# houston.net
KiCad netlist of a schematic drawn in EAGLE
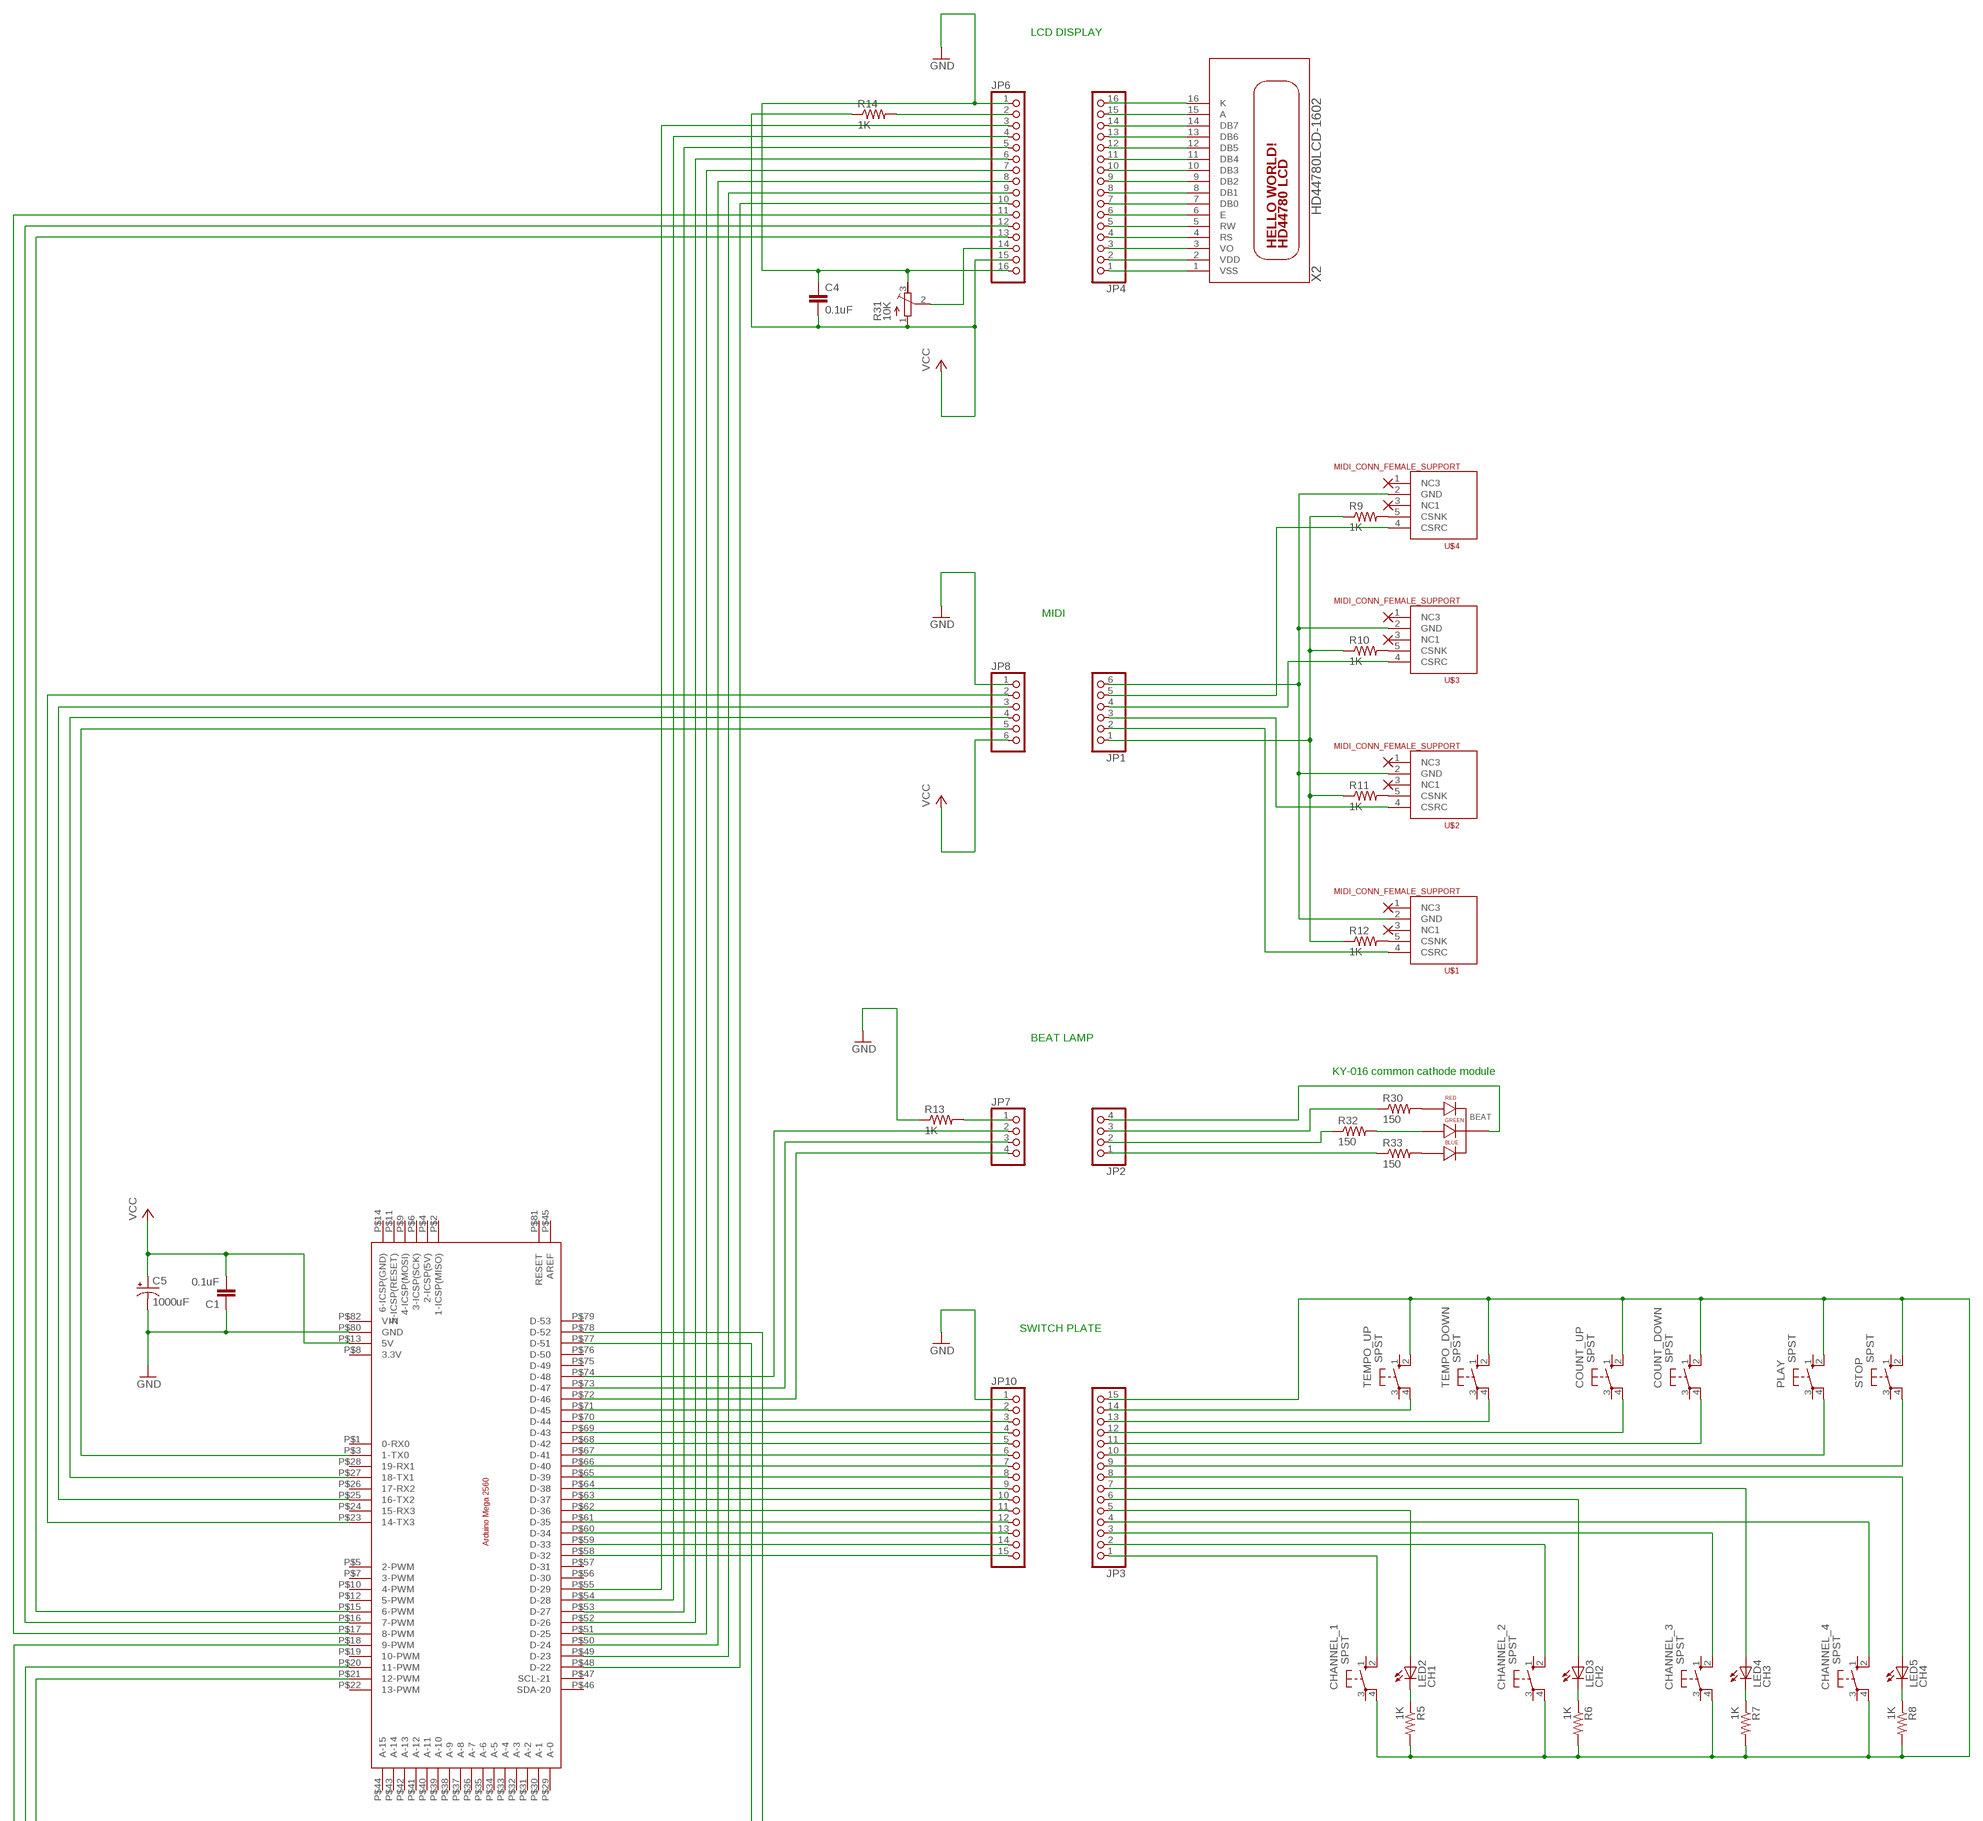
[diagram p0: schematic, sheet 1, part 1 of 3]
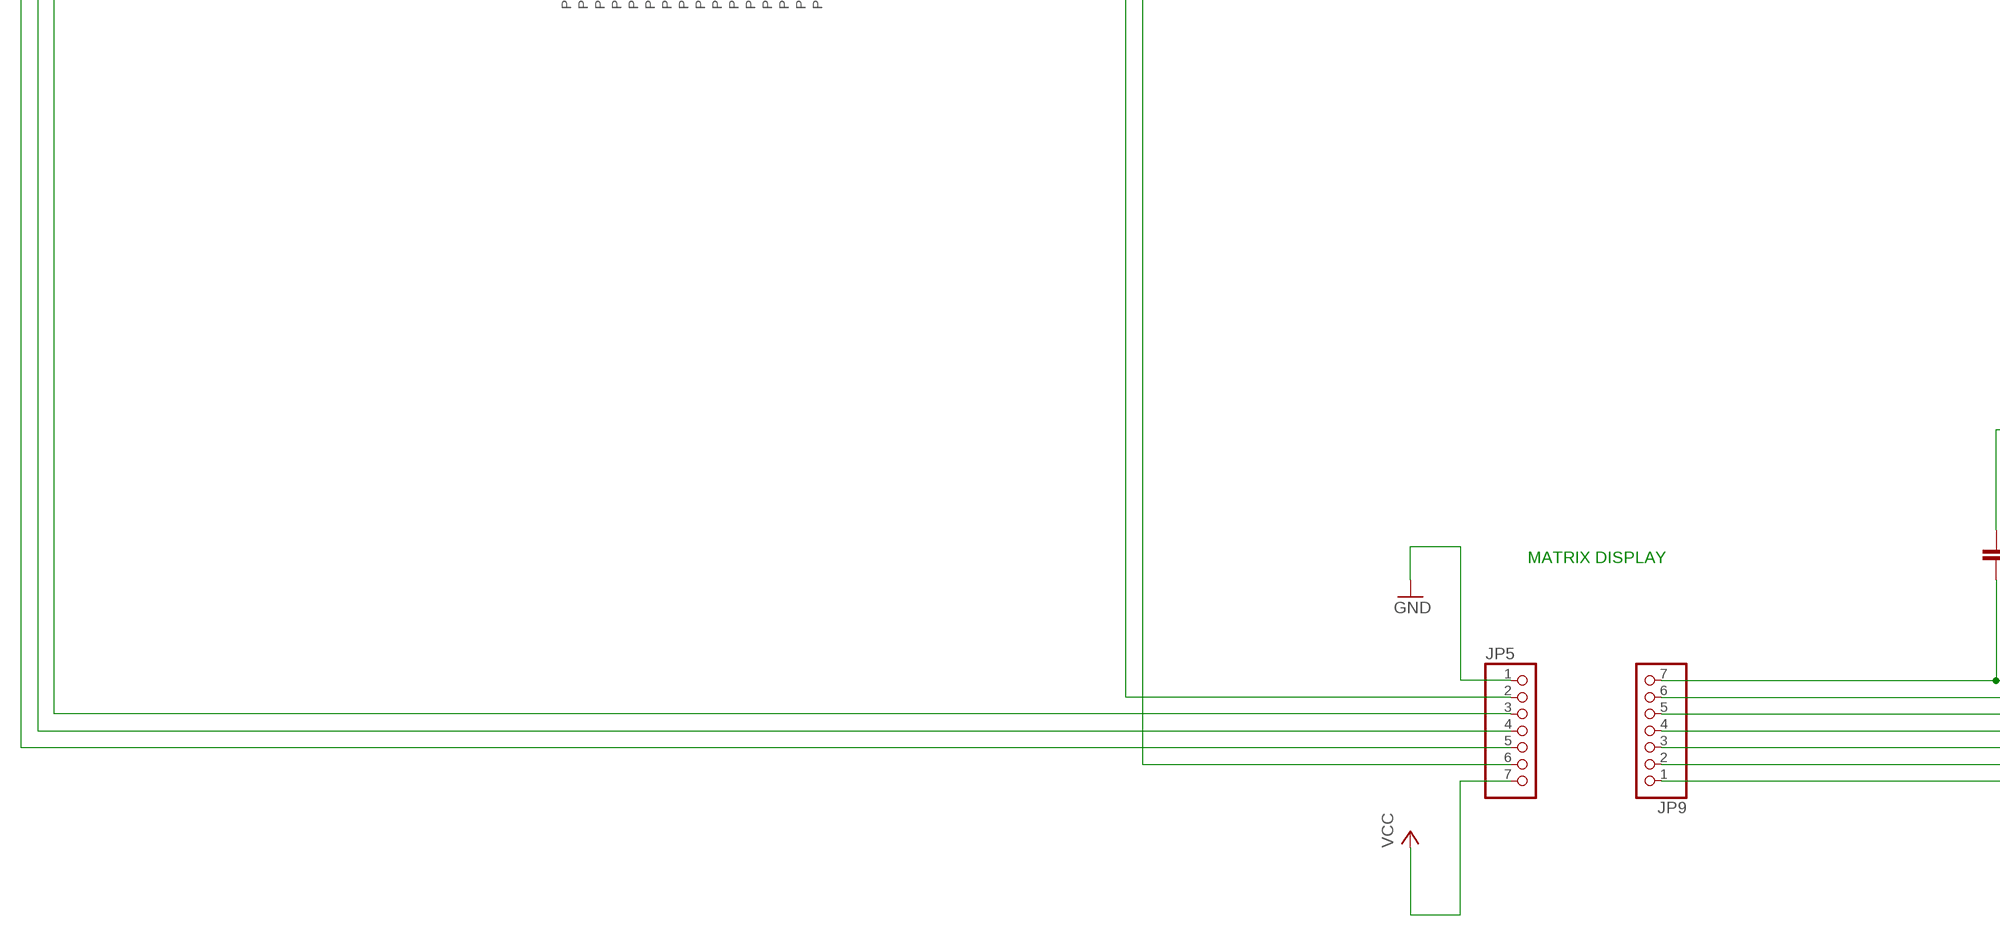
[diagram p1: schematic, sheet 1, part 2 of 3]
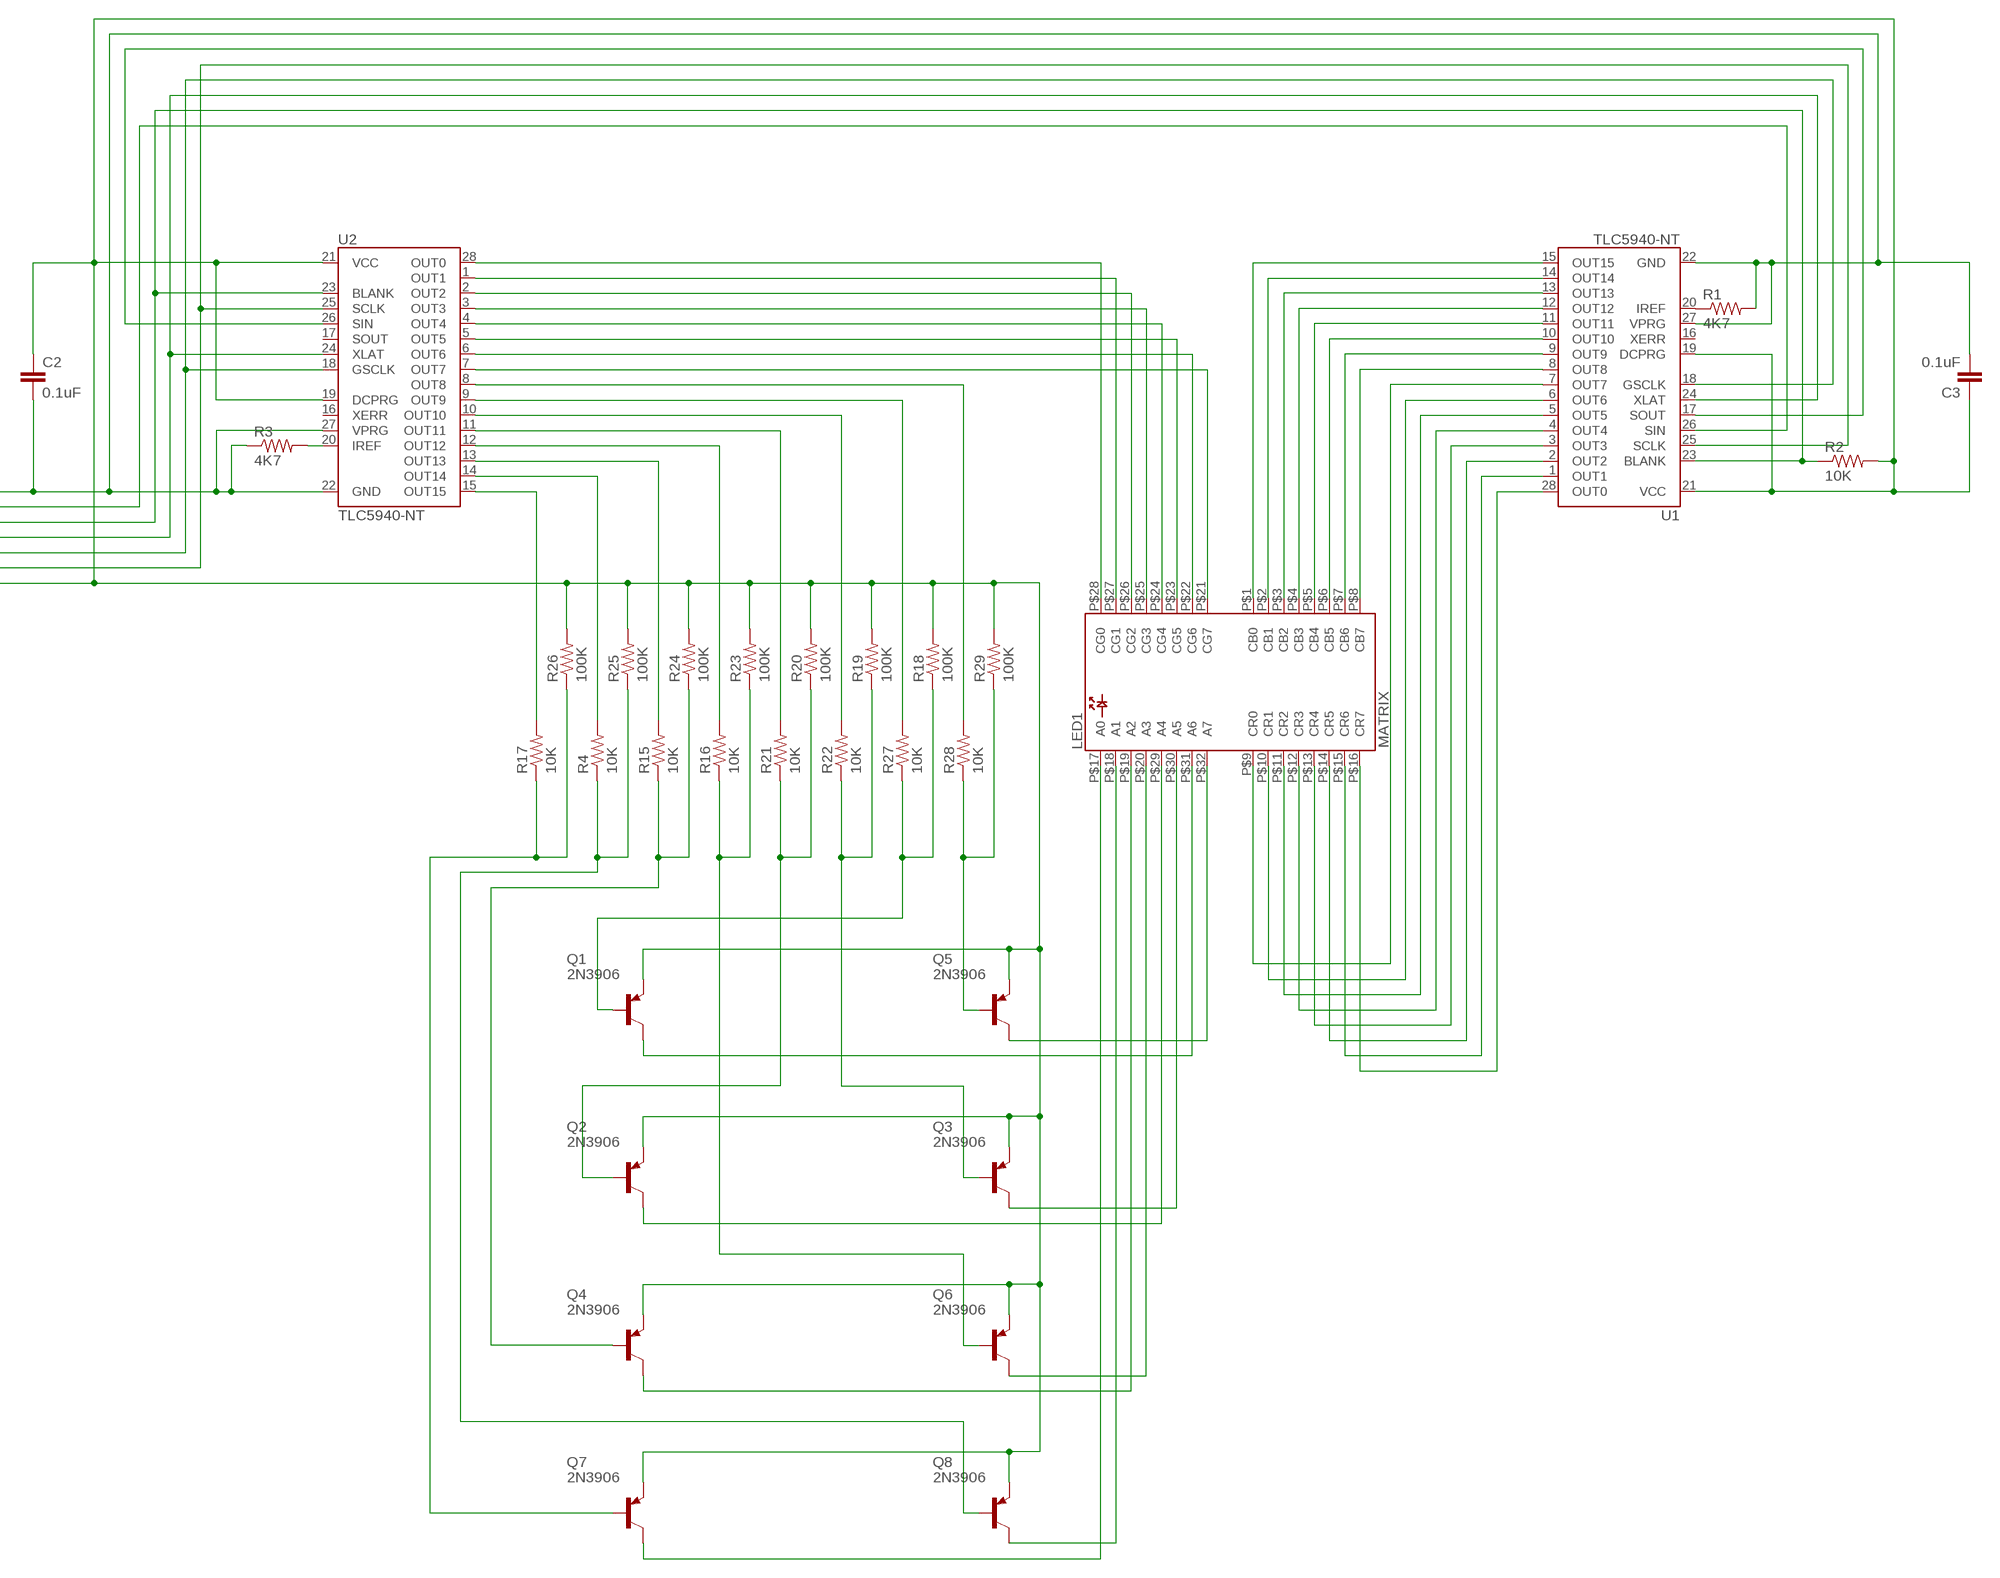
[diagram p2: schematic, sheet 1, part 3 of 3]

(export (version "E")
  (design (tool "Eeschema 10.0.6"))
  (components
    (comp (ref "BEAT")
      (value "LED-RGB-CC-THRUCLEAR")
      (footprint "eagle-import:LED-RGB-THRU")
      (libsource (lib "eagle-import") (part "LED-RGB-CC-THRUCLEAR"))
    )
    (comp (ref "C1")
      (value "0.1uF")
      (footprint "eagle-import:CAP-PTH-SMALLEZ")
      (libsource (lib "eagle-import") (part "CAPEZ"))
    )
    (comp (ref "C2")
      (value "0.1uF")
      (footprint "eagle-import:CAP-PTH-SMALLEZ")
      (libsource (lib "eagle-import") (part "CAPEZ"))
    )
    (comp (ref "C3")
      (value "0.1uF")
      (footprint "eagle-import:CAP-PTH-SMALLEZ")
      (libsource (lib "eagle-import") (part "CAPEZ"))
    )
    (comp (ref "C4")
      (value "0.1uF")
      (footprint "eagle-import:CAP-PTH-SMALLEZ")
      (libsource (lib "eagle-import") (part "CAPEZ"))
    )
    (comp (ref "C5")
      (value "1000uF")
      (footprint "eagle-import:CPOL-RADIAL-1000UF-25V")
      (libsource (lib "eagle-import") (part "CAP_POLPTH4"))
    )
    (comp (ref "CHANNEL_1")
      (value "SPST")
      (footprint "eagle-import:B3F-40XX-ROUND")
      (libsource (lib "eagle-import") (part "40-XX-ROUND"))
    )
    (comp (ref "CHANNEL_2")
      (value "SPST")
      (footprint "eagle-import:B3F-40XX-ROUND")
      (libsource (lib "eagle-import") (part "40-XX-ROUND"))
    )
    (comp (ref "CHANNEL_3")
      (value "SPST")
      (footprint "eagle-import:B3F-40XX-ROUND")
      (libsource (lib "eagle-import") (part "40-XX-ROUND"))
    )
    (comp (ref "CHANNEL_4")
      (value "SPST")
      (footprint "eagle-import:B3F-40XX-ROUND")
      (libsource (lib "eagle-import") (part "40-XX-ROUND"))
    )
    (comp (ref "COUNT_DOWN")
      (value "SPST")
      (footprint "eagle-import:B3F-40XX-ROUND")
      (libsource (lib "eagle-import") (part "40-XX-ROUND"))
    )
    (comp (ref "COUNT_UP")
      (value "SPST")
      (footprint "eagle-import:B3F-40XX-ROUND")
      (libsource (lib "eagle-import") (part "40-XX-ROUND"))
    )
    (comp (ref "JP1")
      (value "PINHD-1X6/90")
      (footprint "eagle-import:1X06_90")
      (libsource (lib "eagle-import") (part "PINHD-1X6/90"))
    )
    (comp (ref "JP2")
      (value "PINHD-1X4/90")
      (footprint "eagle-import:1X04_90")
      (libsource (lib "eagle-import") (part "PINHD-1X4/90"))
    )
    (comp (ref "JP3")
      (value "PINHD-1X15/90")
      (footprint "eagle-import:1X15_90")
      (libsource (lib "eagle-import") (part "PINHD-1X15/90"))
    )
    (comp (ref "JP4")
      (value "PINHD-1X16")
      (footprint "eagle-import:1X16")
      (libsource (lib "eagle-import") (part "PINHD-1X16"))
    )
    (comp (ref "JP5")
      (value "PINHD-1X7")
      (footprint "eagle-import:1X07")
      (libsource (lib "eagle-import") (part "PINHD-1X7"))
    )
    (comp (ref "JP6")
      (value "PINHD-1X16")
      (footprint "eagle-import:1X16")
      (libsource (lib "eagle-import") (part "PINHD-1X16"))
    )
    (comp (ref "JP7")
      (value "PINHD-1X4")
      (footprint "eagle-import:1X04")
      (libsource (lib "eagle-import") (part "PINHD-1X4"))
    )
    (comp (ref "JP8")
      (value "PINHD-1X6")
      (footprint "eagle-import:1X06")
      (libsource (lib "eagle-import") (part "PINHD-1X6"))
    )
    (comp (ref "JP9")
      (value "PINHD-1X7/90")
      (footprint "eagle-import:1X07_90")
      (libsource (lib "eagle-import") (part "PINHD-1X7/90"))
    )
    (comp (ref "JP10")
      (value "PINHD-1X15-CB")
      (footprint "eagle-import:1X15-CB")
      (libsource (lib "eagle-import") (part "PINHD-1X15-CB"))
    )
    (comp (ref "LED1")
      (value "MATRIX")
      (footprint "eagle-import:ORM-2088-RGB-5")
      (libsource (lib "eagle-import") (part "ORM-2088-RGB-5"))
    )
    (comp (ref "LED2")
      (value "CH1")
      (footprint "eagle-import:LED3MM")
      (libsource (lib "eagle-import") (part "LED3MM"))
    )
    (comp (ref "LED3")
      (value "CH2")
      (footprint "eagle-import:LED3MM")
      (libsource (lib "eagle-import") (part "LED3MM"))
    )
    (comp (ref "LED4")
      (value "CH3")
      (footprint "eagle-import:LED3MM")
      (libsource (lib "eagle-import") (part "LED3MM"))
    )
    (comp (ref "LED5")
      (value "CH4")
      (footprint "eagle-import:LED3MM")
      (libsource (lib "eagle-import") (part "LED3MM"))
    )
    (comp (ref "PLAY")
      (value "SPST")
      (footprint "eagle-import:B3F-40XX-ROUND")
      (libsource (lib "eagle-import") (part "40-XX-ROUND"))
    )
    (comp (ref "Q1")
      (value "2N3906")
      (footprint "eagle-import:TO92")
      (libsource (lib "eagle-import") (part "2N3906"))
    )
    (comp (ref "Q2")
      (value "2N3906")
      (footprint "eagle-import:TO92")
      (libsource (lib "eagle-import") (part "2N3906"))
    )
    (comp (ref "Q3")
      (value "2N3906")
      (footprint "eagle-import:TO92")
      (libsource (lib "eagle-import") (part "2N3906"))
    )
    (comp (ref "Q4")
      (value "2N3906")
      (footprint "eagle-import:TO92")
      (libsource (lib "eagle-import") (part "2N3906"))
    )
    (comp (ref "Q5")
      (value "2N3906")
      (footprint "eagle-import:TO92")
      (libsource (lib "eagle-import") (part "2N3906"))
    )
    (comp (ref "Q6")
      (value "2N3906")
      (footprint "eagle-import:TO92")
      (libsource (lib "eagle-import") (part "2N3906"))
    )
    (comp (ref "Q7")
      (value "2N3906")
      (footprint "eagle-import:TO92")
      (libsource (lib "eagle-import") (part "2N3906"))
    )
    (comp (ref "Q8")
      (value "2N3906")
      (footprint "eagle-import:TO92")
      (libsource (lib "eagle-import") (part "2N3906"))
    )
    (comp (ref "R1")
      (value "4K7")
      (footprint "eagle-import:0411V")
      (libsource (lib "eagle-import") (part "R-US_0411/3V"))
    )
    (comp (ref "R2")
      (value "10K")
      (footprint "eagle-import:0411V")
      (libsource (lib "eagle-import") (part "R-US_0411/3V"))
    )
    (comp (ref "R3")
      (value "4K7")
      (footprint "eagle-import:0411V")
      (libsource (lib "eagle-import") (part "R-US_0411/3V"))
    )
    (comp (ref "R4")
      (value "10K")
      (footprint "eagle-import:0207_10")
      (libsource (lib "eagle-import") (part "resistor_R-US_0207/10"))
    )
    (comp (ref "R5")
      (value "1K")
      (footprint "eagle-import:0204_7")
      (libsource (lib "eagle-import") (part "resistor_R-US_0204/7"))
    )
    (comp (ref "R6")
      (value "1K")
      (footprint "eagle-import:0204_7")
      (libsource (lib "eagle-import") (part "resistor_R-US_0204/7"))
    )
    (comp (ref "R7")
      (value "1K")
      (footprint "eagle-import:0204_7")
      (libsource (lib "eagle-import") (part "resistor_R-US_0204/7"))
    )
    (comp (ref "R8")
      (value "1K")
      (footprint "eagle-import:0204_7")
      (libsource (lib "eagle-import") (part "resistor_R-US_0204/7"))
    )
    (comp (ref "R9")
      (value "1K")
      (footprint "eagle-import:0207_2V")
      (libsource (lib "eagle-import") (part "resistor_R-US_0207/2V"))
    )
    (comp (ref "R10")
      (value "1K")
      (footprint "eagle-import:0207_2V")
      (libsource (lib "eagle-import") (part "resistor_R-US_0207/2V"))
    )
    (comp (ref "R11")
      (value "1K")
      (footprint "eagle-import:0207_2V")
      (libsource (lib "eagle-import") (part "resistor_R-US_0207/2V"))
    )
    (comp (ref "R12")
      (value "1K")
      (footprint "eagle-import:0207_2V")
      (libsource (lib "eagle-import") (part "resistor_R-US_0207/2V"))
    )
    (comp (ref "R13")
      (value "1K")
      (footprint "eagle-import:0207_2V")
      (libsource (lib "eagle-import") (part "resistor_R-US_0207/2V"))
    )
    (comp (ref "R14")
      (value "1K")
      (footprint "eagle-import:0204_7")
      (libsource (lib "eagle-import") (part "rcl_R-US_0204/7"))
    )
    (comp (ref "R15")
      (value "10K")
      (footprint "eagle-import:0207_10")
      (libsource (lib "eagle-import") (part "resistor_R-US_0207/10"))
    )
    (comp (ref "R16")
      (value "10K")
      (footprint "eagle-import:0207_10")
      (libsource (lib "eagle-import") (part "resistor_R-US_0207/10"))
    )
    (comp (ref "R17")
      (value "10K")
      (footprint "eagle-import:0207_10")
      (libsource (lib "eagle-import") (part "resistor_R-US_0207/10"))
    )
    (comp (ref "R18")
      (value "100K")
      (footprint "eagle-import:0207_10")
      (libsource (lib "eagle-import") (part "resistor_R-US_0207/10"))
    )
    (comp (ref "R19")
      (value "100K")
      (footprint "eagle-import:0207_10")
      (libsource (lib "eagle-import") (part "resistor_R-US_0207/10"))
    )
    (comp (ref "R20")
      (value "100K")
      (footprint "eagle-import:0207_10")
      (libsource (lib "eagle-import") (part "resistor_R-US_0207/10"))
    )
    (comp (ref "R21")
      (value "10K")
      (footprint "eagle-import:0207_10")
      (libsource (lib "eagle-import") (part "resistor_R-US_0207/10"))
    )
    (comp (ref "R22")
      (value "10K")
      (footprint "eagle-import:0207_10")
      (libsource (lib "eagle-import") (part "resistor_R-US_0207/10"))
    )
    (comp (ref "R23")
      (value "100K")
      (footprint "eagle-import:0207_10")
      (libsource (lib "eagle-import") (part "resistor_R-US_0207/10"))
    )
    (comp (ref "R24")
      (value "100K")
      (footprint "eagle-import:0207_10")
      (libsource (lib "eagle-import") (part "resistor_R-US_0207/10"))
    )
    (comp (ref "R25")
      (value "100K")
      (footprint "eagle-import:0207_10")
      (libsource (lib "eagle-import") (part "resistor_R-US_0207/10"))
    )
    (comp (ref "R26")
      (value "100K")
      (footprint "eagle-import:0207_10")
      (libsource (lib "eagle-import") (part "resistor_R-US_0207/10"))
    )
    (comp (ref "R27")
      (value "10K")
      (footprint "eagle-import:0207_10")
      (libsource (lib "eagle-import") (part "resistor_R-US_0207/10"))
    )
    (comp (ref "R28")
      (value "10K")
      (footprint "eagle-import:0207_10")
      (libsource (lib "eagle-import") (part "resistor_R-US_0207/10"))
    )
    (comp (ref "R29")
      (value "100K")
      (footprint "eagle-import:0207_10")
      (libsource (lib "eagle-import") (part "resistor_R-US_0207/10"))
    )
    (comp (ref "R30")
      (value "150")
      (footprint "eagle-import:0204_7")
      (libsource (lib "eagle-import") (part "R-US_0204/7"))
    )
    (comp (ref "R31")
      (value "10K")
      (footprint "eagle-import:RTRIM3296W")
      (libsource (lib "eagle-import") (part "R-TRIMM3296W"))
    )
    (comp (ref "R32")
      (value "150")
      (footprint "eagle-import:0204_7")
      (libsource (lib "eagle-import") (part "R-US_0204/7"))
    )
    (comp (ref "R33")
      (value "150")
      (footprint "eagle-import:0204_7")
      (libsource (lib "eagle-import") (part "R-US_0204/7"))
    )
    (comp (ref "STOP")
      (value "SPST")
      (footprint "eagle-import:B3F-40XX-ROUND")
      (libsource (lib "eagle-import") (part "40-XX-ROUND"))
    )
    (comp (ref "TEMPO_DOWN")
      (value "SPST")
      (footprint "eagle-import:B3F-40XX-ROUND")
      (libsource (lib "eagle-import") (part "40-XX-ROUND"))
    )
    (comp (ref "TEMPO_UP")
      (value "SPST")
      (footprint "eagle-import:B3F-40XX-ROUND")
      (libsource (lib "eagle-import") (part "40-XX-ROUND"))
    )
    (comp (ref "U$1")
      (value "MIDI_CONN_FEMALE_SUPPORT")
      (footprint "eagle-import:DIN_5_FEMALE_SUPPORT")
      (libsource (lib "eagle-import") (part "MIDI_CONN_FEMALE_SUPPORT"))
    )
    (comp (ref "U$2")
      (value "MIDI_CONN_FEMALE_SUPPORT")
      (footprint "eagle-import:DIN_5_FEMALE_SUPPORT")
      (libsource (lib "eagle-import") (part "MIDI_CONN_FEMALE_SUPPORT"))
    )
    (comp (ref "U$3")
      (value "MIDI_CONN_FEMALE_SUPPORT")
      (footprint "eagle-import:DIN_5_FEMALE_SUPPORT")
      (libsource (lib "eagle-import") (part "MIDI_CONN_FEMALE_SUPPORT"))
    )
    (comp (ref "U$4")
      (value "MIDI_CONN_FEMALE_SUPPORT")
      (footprint "eagle-import:DIN_5_FEMALE_SUPPORT")
      (libsource (lib "eagle-import") (part "MIDI_CONN_FEMALE_SUPPORT"))
    )
    (comp (ref "U$6")
      (value "2560")
      (footprint "eagle-import:MEDUINO2560")
      (libsource (lib "eagle-import") (part "2560"))
    )
    (comp (ref "U1")
      (value "TLC5940-NT")
      (footprint "eagle-import:DIL28-3")
      (libsource (lib "eagle-import") (part "TLC5940-NT"))
    )
    (comp (ref "U2")
      (value "TLC5940-NT")
      (footprint "eagle-import:DIL28-3")
      (libsource (lib "eagle-import") (part "TLC5940-NT"))
    )
    (comp (ref "X2")
      (value "HD44780LCD-1602")
      (footprint "eagle-import:LCD1602")
      (libsource (lib "eagle-import") (part "HD44780LCD-1602"))
    )
  )
  (nets
    (net (code "1") (name "GND") (class "Default")
      (node (ref "C1") (pin "1") (pinfunction "1_1") (pintype "passive"))
      (node (ref "C4") (pin "1") (pinfunction "1_1") (pintype "passive"))
      (node (ref "C5") (pin "2") (pinfunction "-_2") (pintype "passive"))
      (node (ref "JP10") (pin "1") (pinfunction "1_1") (pintype "passive"))
      (node (ref "JP5") (pin "1") (pinfunction "1_1") (pintype "passive"))
      (node (ref "JP6") (pin "1") (pinfunction "1_1") (pintype "passive"))
      (node (ref "JP6") (pin "16") (pinfunction "16_16") (pintype "passive"))
      (node (ref "JP8") (pin "1") (pinfunction "1_1") (pintype "passive"))
      (node (ref "R13") (pin "1") (pinfunction "1_1") (pintype "passive"))
      (node (ref "R31") (pin "3") (pinfunction "E_3") (pintype "passive"))
      (node (ref "U$6") (pin "P$80") (pinfunction "GND_P$80") (pintype "bidirectional"))
    )
    (net (code "2") (name "Net-(BEAT-BLUE_CATHODE)") (class "Default")
      (node (ref "BEAT") (pin "4") (pinfunction "BLUE_CATHODE_4") (pintype "bidirectional"))
      (node (ref "R33") (pin "2") (pinfunction "2_2") (pintype "passive"))
    )
    (net (code "3") (name "Net-(BEAT-CATHODE)") (class "Default")
      (node (ref "BEAT") (pin "2") (pinfunction "CATHODE_2") (pintype "bidirectional"))
      (node (ref "JP2") (pin "4") (pinfunction "4_4") (pintype "passive"))
    )
    (net (code "4") (name "Net-(BEAT-GREEN_CATHODE)") (class "Default")
      (node (ref "BEAT") (pin "3") (pinfunction "GREEN_CATHODE_3") (pintype "bidirectional"))
      (node (ref "R32") (pin "2") (pinfunction "2_2") (pintype "passive"))
    )
    (net (code "5") (name "Net-(BEAT-RED_CATHODE)") (class "Default")
      (node (ref "BEAT") (pin "1") (pinfunction "RED_CATHODE_1") (pintype "bidirectional"))
      (node (ref "R30") (pin "2") (pinfunction "2_2") (pintype "passive"))
    )
    (net (code "6") (name "Net-(CHANNEL_1-P1)") (class "Default")
      (node (ref "CHANNEL_1") (pin "4") (pinfunction "P1_4") (pintype "passive"))
      (node (ref "CHANNEL_2") (pin "4") (pinfunction "P1_4") (pintype "passive"))
      (node (ref "CHANNEL_3") (pin "4") (pinfunction "P1_4") (pintype "passive"))
      (node (ref "CHANNEL_4") (pin "4") (pinfunction "P1_4") (pintype "passive"))
      (node (ref "COUNT_DOWN") (pin "2") (pinfunction "S1_2") (pintype "passive"))
      (node (ref "COUNT_UP") (pin "2") (pinfunction "S1_2") (pintype "passive"))
      (node (ref "JP3") (pin "15") (pinfunction "15_15") (pintype "passive"))
      (node (ref "PLAY") (pin "2") (pinfunction "S1_2") (pintype "passive"))
      (node (ref "R5") (pin "2") (pinfunction "2_2") (pintype "passive"))
      (node (ref "R6") (pin "2") (pinfunction "2_2") (pintype "passive"))
      (node (ref "R7") (pin "2") (pinfunction "2_2") (pintype "passive"))
      (node (ref "R8") (pin "2") (pinfunction "2_2") (pintype "passive"))
      (node (ref "STOP") (pin "2") (pinfunction "S1_2") (pintype "passive"))
      (node (ref "TEMPO_DOWN") (pin "2") (pinfunction "S1_2") (pintype "passive"))
      (node (ref "TEMPO_UP") (pin "2") (pinfunction "S1_2") (pintype "passive"))
    )
    (net (code "7") (name "Net-(CHANNEL_1-S1)") (class "Default")
      (node (ref "CHANNEL_1") (pin "2") (pinfunction "S1_2") (pintype "passive"))
      (node (ref "JP3") (pin "1") (pinfunction "1_1") (pintype "passive"))
    )
    (net (code "8") (name "Net-(CHANNEL_2-S1)") (class "Default")
      (node (ref "CHANNEL_2") (pin "2") (pinfunction "S1_2") (pintype "passive"))
      (node (ref "JP3") (pin "2") (pinfunction "2_2") (pintype "passive"))
    )
    (net (code "9") (name "Net-(CHANNEL_3-S1)") (class "Default")
      (node (ref "CHANNEL_3") (pin "2") (pinfunction "S1_2") (pintype "passive"))
      (node (ref "JP3") (pin "3") (pinfunction "3_3") (pintype "passive"))
    )
    (net (code "10") (name "Net-(CHANNEL_4-S1)") (class "Default")
      (node (ref "CHANNEL_4") (pin "2") (pinfunction "S1_2") (pintype "passive"))
      (node (ref "JP3") (pin "4") (pinfunction "4_4") (pintype "passive"))
    )
    (net (code "11") (name "Net-(COUNT_DOWN-P1)") (class "Default")
      (node (ref "COUNT_DOWN") (pin "4") (pinfunction "P1_4") (pintype "passive"))
      (node (ref "JP3") (pin "11") (pinfunction "11_11") (pintype "passive"))
    )
    (net (code "12") (name "Net-(COUNT_UP-P1)") (class "Default")
      (node (ref "COUNT_UP") (pin "4") (pinfunction "P1_4") (pintype "passive"))
      (node (ref "JP3") (pin "12") (pinfunction "12_12") (pintype "passive"))
    )
    (net (code "13") (name "Net-(JP1-Pad1)") (class "Default")
      (node (ref "JP1") (pin "1") (pinfunction "1_1") (pintype "passive"))
      (node (ref "R10") (pin "1") (pinfunction "1_1") (pintype "passive"))
      (node (ref "R11") (pin "1") (pinfunction "1_1") (pintype "passive"))
      (node (ref "R12") (pin "1") (pinfunction "1_1") (pintype "passive"))
      (node (ref "R9") (pin "1") (pinfunction "1_1") (pintype "passive"))
    )
    (net (code "14") (name "Net-(JP2-Pad1)") (class "Default")
      (node (ref "JP2") (pin "1") (pinfunction "1_1") (pintype "passive"))
      (node (ref "R33") (pin "1") (pinfunction "1_1") (pintype "passive"))
    )
    (net (code "15") (name "Net-(JP2-Pad2)") (class "Default")
      (node (ref "JP2") (pin "2") (pinfunction "2_2") (pintype "passive"))
      (node (ref "R32") (pin "1") (pinfunction "1_1") (pintype "passive"))
    )
    (net (code "16") (name "Net-(JP2-Pad3)") (class "Default")
      (node (ref "JP2") (pin "3") (pinfunction "3_3") (pintype "passive"))
      (node (ref "R30") (pin "1") (pinfunction "1_1") (pintype "passive"))
    )
    (net (code "17") (name "Net-(JP3-Pad5)") (class "Default")
      (node (ref "JP3") (pin "5") (pinfunction "5_5") (pintype "passive"))
      (node (ref "LED2") (pin "A") (pinfunction "A_A") (pintype "passive"))
    )
    (net (code "18") (name "Net-(JP3-Pad6)") (class "Default")
      (node (ref "JP3") (pin "6") (pinfunction "6_6") (pintype "passive"))
      (node (ref "LED3") (pin "A") (pinfunction "A_A") (pintype "passive"))
    )
    (net (code "19") (name "Net-(JP3-Pad7)") (class "Default")
      (node (ref "JP3") (pin "7") (pinfunction "7_7") (pintype "passive"))
      (node (ref "LED4") (pin "A") (pinfunction "A_A") (pintype "passive"))
    )
    (net (code "20") (name "Net-(JP3-Pad8)") (class "Default")
      (node (ref "JP3") (pin "8") (pinfunction "8_8") (pintype "passive"))
      (node (ref "LED5") (pin "A") (pinfunction "A_A") (pintype "passive"))
    )
    (net (code "21") (name "Net-(JP6-Pad2)") (class "Default")
      (node (ref "JP6") (pin "2") (pinfunction "2_2") (pintype "passive"))
      (node (ref "R14") (pin "2") (pinfunction "2_2") (pintype "passive"))
    )
    (net (code "22") (name "Net-(JP7-Pad1)") (class "Default")
      (node (ref "JP7") (pin "1") (pinfunction "1_1") (pintype "passive"))
      (node (ref "R13") (pin "2") (pinfunction "2_2") (pintype "passive"))
    )
    (net (code "23") (name "Net-(LED1-A0)") (class "Default")
      (node (ref "LED1") (pin "P$17") (pinfunction "A0_P$17") (pintype "bidirectional"))
      (node (ref "Q7") (pin "1") (pinfunction "C_1") (pintype "passive"))
    )
    (net (code "24") (name "Net-(LED1-A1)") (class "Default")
      (node (ref "LED1") (pin "P$18") (pinfunction "A1_P$18") (pintype "bidirectional"))
      (node (ref "Q8") (pin "1") (pinfunction "C_1") (pintype "passive"))
    )
    (net (code "25") (name "Net-(LED1-A2)") (class "Default")
      (node (ref "LED1") (pin "P$19") (pinfunction "A2_P$19") (pintype "bidirectional"))
      (node (ref "Q4") (pin "1") (pinfunction "C_1") (pintype "passive"))
    )
    (net (code "26") (name "Net-(LED1-A3)") (class "Default")
      (node (ref "LED1") (pin "P$20") (pinfunction "A3_P$20") (pintype "bidirectional"))
      (node (ref "Q6") (pin "1") (pinfunction "C_1") (pintype "passive"))
    )
    (net (code "27") (name "Net-(LED1-A4)") (class "Default")
      (node (ref "LED1") (pin "P$29") (pinfunction "A4_P$29") (pintype "bidirectional"))
      (node (ref "Q2") (pin "1") (pinfunction "C_1") (pintype "passive"))
    )
    (net (code "28") (name "Net-(LED1-A5)") (class "Default")
      (node (ref "LED1") (pin "P$30") (pinfunction "A5_P$30") (pintype "bidirectional"))
      (node (ref "Q3") (pin "1") (pinfunction "C_1") (pintype "passive"))
    )
    (net (code "29") (name "Net-(LED1-A6)") (class "Default")
      (node (ref "LED1") (pin "P$31") (pinfunction "A6_P$31") (pintype "bidirectional"))
      (node (ref "Q1") (pin "1") (pinfunction "C_1") (pintype "passive"))
    )
    (net (code "30") (name "Net-(LED1-A7)") (class "Default")
      (node (ref "LED1") (pin "P$32") (pinfunction "A7_P$32") (pintype "bidirectional"))
      (node (ref "Q5") (pin "1") (pinfunction "C_1") (pintype "passive"))
    )
    (net (code "31") (name "Net-(LED1-CB0)") (class "Default")
      (node (ref "LED1") (pin "P$1") (pinfunction "CB0_P$1") (pintype "bidirectional"))
      (node (ref "U1") (pin "15") (pinfunction "OUT15_15") (pintype "bidirectional"))
    )
    (net (code "32") (name "Net-(LED1-CB1)") (class "Default")
      (node (ref "LED1") (pin "P$2") (pinfunction "CB1_P$2") (pintype "bidirectional"))
      (node (ref "U1") (pin "14") (pinfunction "OUT14_14") (pintype "bidirectional"))
    )
    (net (code "33") (name "Net-(LED1-CB2)") (class "Default")
      (node (ref "LED1") (pin "P$3") (pinfunction "CB2_P$3") (pintype "bidirectional"))
      (node (ref "U1") (pin "13") (pinfunction "OUT13_13") (pintype "bidirectional"))
    )
    (net (code "34") (name "Net-(LED1-CB3)") (class "Default")
      (node (ref "LED1") (pin "P$4") (pinfunction "CB3_P$4") (pintype "bidirectional"))
      (node (ref "U1") (pin "12") (pinfunction "OUT12_12") (pintype "bidirectional"))
    )
    (net (code "35") (name "Net-(LED1-CB4)") (class "Default")
      (node (ref "LED1") (pin "P$5") (pinfunction "CB4_P$5") (pintype "bidirectional"))
      (node (ref "U1") (pin "11") (pinfunction "OUT11_11") (pintype "bidirectional"))
    )
    (net (code "36") (name "Net-(LED1-CB5)") (class "Default")
      (node (ref "LED1") (pin "P$6") (pinfunction "CB5_P$6") (pintype "bidirectional"))
      (node (ref "U1") (pin "10") (pinfunction "OUT10_10") (pintype "bidirectional"))
    )
    (net (code "37") (name "Net-(LED1-CB6)") (class "Default")
      (node (ref "LED1") (pin "P$7") (pinfunction "CB6_P$7") (pintype "bidirectional"))
      (node (ref "U1") (pin "9") (pinfunction "OUT9_9") (pintype "bidirectional"))
    )
    (net (code "38") (name "Net-(LED1-CB7)") (class "Default")
      (node (ref "LED1") (pin "P$8") (pinfunction "CB7_P$8") (pintype "bidirectional"))
      (node (ref "U1") (pin "8") (pinfunction "OUT8_8") (pintype "bidirectional"))
    )
    (net (code "39") (name "Net-(LED1-CG0)") (class "Default")
      (node (ref "LED1") (pin "P$28") (pinfunction "CG0_P$28") (pintype "bidirectional"))
      (node (ref "U2") (pin "28") (pinfunction "OUT0_28") (pintype "bidirectional"))
    )
    (net (code "40") (name "Net-(LED1-CG1)") (class "Default")
      (node (ref "LED1") (pin "P$27") (pinfunction "CG1_P$27") (pintype "bidirectional"))
      (node (ref "U2") (pin "1") (pinfunction "OUT1_1") (pintype "bidirectional"))
    )
    (net (code "41") (name "Net-(LED1-CG2)") (class "Default")
      (node (ref "LED1") (pin "P$26") (pinfunction "CG2_P$26") (pintype "bidirectional"))
      (node (ref "U2") (pin "2") (pinfunction "OUT2_2") (pintype "bidirectional"))
    )
    (net (code "42") (name "Net-(LED1-CG3)") (class "Default")
      (node (ref "LED1") (pin "P$25") (pinfunction "CG3_P$25") (pintype "bidirectional"))
      (node (ref "U2") (pin "3") (pinfunction "OUT3_3") (pintype "bidirectional"))
    )
    (net (code "43") (name "Net-(LED1-CG4)") (class "Default")
      (node (ref "LED1") (pin "P$24") (pinfunction "CG4_P$24") (pintype "bidirectional"))
      (node (ref "U2") (pin "4") (pinfunction "OUT4_4") (pintype "bidirectional"))
    )
    (net (code "44") (name "Net-(LED1-CG5)") (class "Default")
      (node (ref "LED1") (pin "P$23") (pinfunction "CG5_P$23") (pintype "bidirectional"))
      (node (ref "U2") (pin "5") (pinfunction "OUT5_5") (pintype "bidirectional"))
    )
    (net (code "45") (name "Net-(LED1-CG6)") (class "Default")
      (node (ref "LED1") (pin "P$22") (pinfunction "CG6_P$22") (pintype "bidirectional"))
      (node (ref "U2") (pin "6") (pinfunction "OUT6_6") (pintype "bidirectional"))
    )
    (net (code "46") (name "Net-(LED1-CG7)") (class "Default")
      (node (ref "LED1") (pin "P$21") (pinfunction "CG7_P$21") (pintype "bidirectional"))
      (node (ref "U2") (pin "7") (pinfunction "OUT7_7") (pintype "bidirectional"))
    )
    (net (code "47") (name "Net-(LED1-CR0)") (class "Default")
      (node (ref "LED1") (pin "P$9") (pinfunction "CR0_P$9") (pintype "bidirectional"))
      (node (ref "U1") (pin "7") (pinfunction "OUT7_7") (pintype "bidirectional"))
    )
    (net (code "48") (name "Net-(LED1-CR1)") (class "Default")
      (node (ref "LED1") (pin "P$10") (pinfunction "CR1_P$10") (pintype "bidirectional"))
      (node (ref "U1") (pin "6") (pinfunction "OUT6_6") (pintype "bidirectional"))
    )
    (net (code "49") (name "Net-(LED1-CR2)") (class "Default")
      (node (ref "LED1") (pin "P$11") (pinfunction "CR2_P$11") (pintype "bidirectional"))
      (node (ref "U1") (pin "5") (pinfunction "OUT5_5") (pintype "bidirectional"))
    )
    (net (code "50") (name "Net-(LED1-CR3)") (class "Default")
      (node (ref "LED1") (pin "P$12") (pinfunction "CR3_P$12") (pintype "bidirectional"))
      (node (ref "U1") (pin "4") (pinfunction "OUT4_4") (pintype "bidirectional"))
    )
    (net (code "51") (name "Net-(LED1-CR4)") (class "Default")
      (node (ref "LED1") (pin "P$13") (pinfunction "CR4_P$13") (pintype "bidirectional"))
      (node (ref "U1") (pin "3") (pinfunction "OUT3_3") (pintype "bidirectional"))
    )
    (net (code "52") (name "Net-(LED1-CR5)") (class "Default")
      (node (ref "LED1") (pin "P$14") (pinfunction "CR5_P$14") (pintype "bidirectional"))
      (node (ref "U1") (pin "2") (pinfunction "OUT2_2") (pintype "bidirectional"))
    )
    (net (code "53") (name "Net-(LED1-CR6)") (class "Default")
      (node (ref "LED1") (pin "P$15") (pinfunction "CR6_P$15") (pintype "bidirectional"))
      (node (ref "U1") (pin "1") (pinfunction "OUT1_1") (pintype "bidirectional"))
    )
    (net (code "54") (name "Net-(LED1-CR7)") (class "Default")
      (node (ref "LED1") (pin "P$16") (pinfunction "CR7_P$16") (pintype "bidirectional"))
      (node (ref "U1") (pin "28") (pinfunction "OUT0_28") (pintype "bidirectional"))
    )
    (net (code "55") (name "Net-(LED2-C)") (class "Default")
      (node (ref "LED2") (pin "K") (pinfunction "C_K") (pintype "passive"))
      (node (ref "R5") (pin "1") (pinfunction "1_1") (pintype "passive"))
    )
    (net (code "56") (name "Net-(LED3-C)") (class "Default")
      (node (ref "LED3") (pin "K") (pinfunction "C_K") (pintype "passive"))
      (node (ref "R6") (pin "1") (pinfunction "1_1") (pintype "passive"))
    )
    (net (code "57") (name "Net-(LED4-C)") (class "Default")
      (node (ref "LED4") (pin "K") (pinfunction "C_K") (pintype "passive"))
      (node (ref "R7") (pin "1") (pinfunction "1_1") (pintype "passive"))
    )
    (net (code "58") (name "Net-(LED5-C)") (class "Default")
      (node (ref "LED5") (pin "K") (pinfunction "C_K") (pintype "passive"))
      (node (ref "R8") (pin "1") (pinfunction "1_1") (pintype "passive"))
    )
    (net (code "59") (name "Net-(PLAY-P1)") (class "Default")
      (node (ref "JP3") (pin "10") (pinfunction "10_10") (pintype "passive"))
      (node (ref "PLAY") (pin "4") (pinfunction "P1_4") (pintype "passive"))
    )
    (net (code "60") (name "Net-(Q1-B)") (class "Default")
      (node (ref "Q1") (pin "2") (pinfunction "B_2") (pintype "passive"))
      (node (ref "R18") (pin "1") (pinfunction "1_1") (pintype "passive"))
      (node (ref "R27") (pin "1") (pinfunction "1_1") (pintype "passive"))
    )
    (net (code "61") (name "Net-(Q1-E)") (class "Default")
      (node (ref "C2") (pin "1") (pinfunction "1_1") (pintype "passive"))
      (node (ref "C3") (pin "1") (pinfunction "1_1") (pintype "passive"))
      (node (ref "JP9") (pin "1") (pinfunction "1_1") (pintype "passive"))
      (node (ref "Q1") (pin "3") (pinfunction "E_3") (pintype "passive"))
      (node (ref "Q2") (pin "3") (pinfunction "E_3") (pintype "passive"))
      (node (ref "Q3") (pin "3") (pinfunction "E_3") (pintype "passive"))
      (node (ref "Q4") (pin "3") (pinfunction "E_3") (pintype "passive"))
      (node (ref "Q5") (pin "3") (pinfunction "E_3") (pintype "passive"))
      (node (ref "Q6") (pin "3") (pinfunction "E_3") (pintype "passive"))
      (node (ref "Q7") (pin "3") (pinfunction "E_3") (pintype "passive"))
      (node (ref "Q8") (pin "3") (pinfunction "E_3") (pintype "passive"))
      (node (ref "R18") (pin "2") (pinfunction "2_2") (pintype "passive"))
      (node (ref "R19") (pin "2") (pinfunction "2_2") (pintype "passive"))
      (node (ref "R2") (pin "2") (pinfunction "2_2") (pintype "passive"))
      (node (ref "R20") (pin "2") (pinfunction "2_2") (pintype "passive"))
      (node (ref "R23") (pin "2") (pinfunction "2_2") (pintype "passive"))
      (node (ref "R24") (pin "2") (pinfunction "2_2") (pintype "passive"))
      (node (ref "R25") (pin "2") (pinfunction "2_2") (pintype "passive"))
      (node (ref "R26") (pin "2") (pinfunction "2_2") (pintype "passive"))
      (node (ref "R29") (pin "2") (pinfunction "2_2") (pintype "passive"))
      (node (ref "U1") (pin "19") (pinfunction "DCPRG_19") (pintype "bidirectional"))
      (node (ref "U1") (pin "21") (pinfunction "VCC_21") (pintype "bidirectional"))
      (node (ref "U2") (pin "19") (pinfunction "DCPRG_19") (pintype "bidirectional"))
      (node (ref "U2") (pin "21") (pinfunction "VCC_21") (pintype "bidirectional"))
    )
    (net (code "62") (name "Net-(Q2-B)") (class "Default")
      (node (ref "Q2") (pin "2") (pinfunction "B_2") (pintype "passive"))
      (node (ref "R20") (pin "1") (pinfunction "1_1") (pintype "passive"))
      (node (ref "R21") (pin "1") (pinfunction "1_1") (pintype "passive"))
    )
    (net (code "63") (name "Net-(Q3-B)") (class "Default")
      (node (ref "Q3") (pin "2") (pinfunction "B_2") (pintype "passive"))
      (node (ref "R19") (pin "1") (pinfunction "1_1") (pintype "passive"))
      (node (ref "R22") (pin "1") (pinfunction "1_1") (pintype "passive"))
    )
    (net (code "64") (name "Net-(Q4-B)") (class "Default")
      (node (ref "Q4") (pin "2") (pinfunction "B_2") (pintype "passive"))
      (node (ref "R15") (pin "1") (pinfunction "1_1") (pintype "passive"))
      (node (ref "R24") (pin "1") (pinfunction "1_1") (pintype "passive"))
    )
    (net (code "65") (name "Net-(Q5-B)") (class "Default")
      (node (ref "Q5") (pin "2") (pinfunction "B_2") (pintype "passive"))
      (node (ref "R28") (pin "1") (pinfunction "1_1") (pintype "passive"))
      (node (ref "R29") (pin "1") (pinfunction "1_1") (pintype "passive"))
    )
    (net (code "66") (name "Net-(Q6-B)") (class "Default")
      (node (ref "Q6") (pin "2") (pinfunction "B_2") (pintype "passive"))
      (node (ref "R16") (pin "1") (pinfunction "1_1") (pintype "passive"))
      (node (ref "R23") (pin "1") (pinfunction "1_1") (pintype "passive"))
    )
    (net (code "67") (name "Net-(Q7-B)") (class "Default")
      (node (ref "Q7") (pin "2") (pinfunction "B_2") (pintype "passive"))
      (node (ref "R17") (pin "1") (pinfunction "1_1") (pintype "passive"))
      (node (ref "R26") (pin "1") (pinfunction "1_1") (pintype "passive"))
    )
    (net (code "68") (name "Net-(Q8-B)") (class "Default")
      (node (ref "Q8") (pin "2") (pinfunction "B_2") (pintype "passive"))
      (node (ref "R25") (pin "1") (pinfunction "1_1") (pintype "passive"))
      (node (ref "R4") (pin "1") (pinfunction "1_1") (pintype "passive"))
    )
    (net (code "69") (name "Net-(R31-S)") (class "Default")
      (node (ref "JP6") (pin "14") (pinfunction "14_14") (pintype "passive"))
      (node (ref "R31") (pin "2") (pinfunction "S_2") (pintype "passive"))
    )
    (net (code "70") (name "Net-(STOP-P1)") (class "Default")
      (node (ref "JP3") (pin "9") (pinfunction "9_9") (pintype "passive"))
      (node (ref "STOP") (pin "4") (pinfunction "P1_4") (pintype "passive"))
    )
    (net (code "71") (name "Net-(TEMPO_DOWN-P1)") (class "Default")
      (node (ref "JP3") (pin "13") (pinfunction "13_13") (pintype "passive"))
      (node (ref "TEMPO_DOWN") (pin "4") (pinfunction "P1_4") (pintype "passive"))
    )
    (net (code "72") (name "Net-(TEMPO_UP-P1)") (class "Default")
      (node (ref "JP3") (pin "14") (pinfunction "14_14") (pintype "passive"))
      (node (ref "TEMPO_UP") (pin "4") (pinfunction "P1_4") (pintype "passive"))
    )
    (net (code "73") (name "Net-(U$1-CSNK)") (class "Default")
      (node (ref "R12") (pin "2") (pinfunction "2_2") (pintype "passive"))
      (node (ref "U$1") (pin "5") (pinfunction "CSNK_5") (pintype "bidirectional"))
    )
    (net (code "74") (name "Net-(U$1-CSRC)") (class "Default")
      (node (ref "JP1") (pin "2") (pinfunction "2_2") (pintype "passive"))
      (node (ref "U$1") (pin "4") (pinfunction "CSRC_4") (pintype "bidirectional"))
    )
    (net (code "75") (name "Net-(U$1-GND)") (class "Default")
      (node (ref "JP1") (pin "6") (pinfunction "6_6") (pintype "passive"))
      (node (ref "U$1") (pin "2") (pinfunction "GND_2") (pintype "bidirectional"))
      (node (ref "U$2") (pin "2") (pinfunction "GND_2") (pintype "bidirectional"))
      (node (ref "U$3") (pin "2") (pinfunction "GND_2") (pintype "bidirectional"))
      (node (ref "U$4") (pin "2") (pinfunction "GND_2") (pintype "bidirectional"))
    )
    (net (code "76") (name "Net-(U$2-CSNK)") (class "Default")
      (node (ref "R11") (pin "2") (pinfunction "2_2") (pintype "passive"))
      (node (ref "U$2") (pin "5") (pinfunction "CSNK_5") (pintype "bidirectional"))
    )
    (net (code "77") (name "Net-(U$2-CSRC)") (class "Default")
      (node (ref "JP1") (pin "3") (pinfunction "3_3") (pintype "passive"))
      (node (ref "U$2") (pin "4") (pinfunction "CSRC_4") (pintype "bidirectional"))
    )
    (net (code "78") (name "Net-(U$3-CSNK)") (class "Default")
      (node (ref "R10") (pin "2") (pinfunction "2_2") (pintype "passive"))
      (node (ref "U$3") (pin "5") (pinfunction "CSNK_5") (pintype "bidirectional"))
    )
    (net (code "79") (name "Net-(U$3-CSRC)") (class "Default")
      (node (ref "JP1") (pin "4") (pinfunction "4_4") (pintype "passive"))
      (node (ref "U$3") (pin "4") (pinfunction "CSRC_4") (pintype "bidirectional"))
    )
    (net (code "80") (name "Net-(U$4-CSNK)") (class "Default")
      (node (ref "R9") (pin "2") (pinfunction "2_2") (pintype "passive"))
      (node (ref "U$4") (pin "5") (pinfunction "CSNK_5") (pintype "bidirectional"))
    )
    (net (code "81") (name "Net-(U$4-CSRC)") (class "Default")
      (node (ref "JP1") (pin "5") (pinfunction "5_5") (pintype "passive"))
      (node (ref "U$4") (pin "4") (pinfunction "CSRC_4") (pintype "bidirectional"))
    )
    (net (code "82") (name "Net-(U$6-1-TX0)") (class "Default")
      (node (ref "JP8") (pin "5") (pinfunction "5_5") (pintype "passive"))
      (node (ref "U$6") (pin "P$3") (pinfunction "1-TX0_P$3") (pintype "bidirectional"))
    )
    (net (code "83") (name "Net-(U$6-6-PWM)") (class "Default")
      (node (ref "JP6") (pin "13") (pinfunction "13_13") (pintype "passive"))
      (node (ref "U$6") (pin "P$15") (pinfunction "6-PWM_P$15") (pintype "bidirectional"))
    )
    (net (code "84") (name "Net-(U$6-7-PWM)") (class "Default")
      (node (ref "JP6") (pin "12") (pinfunction "12_12") (pintype "passive"))
      (node (ref "U$6") (pin "P$16") (pinfunction "7-PWM_P$16") (pintype "bidirectional"))
    )
    (net (code "85") (name "Net-(U$6-8-PWM)") (class "Default")
      (node (ref "JP6") (pin "11") (pinfunction "11_11") (pintype "passive"))
      (node (ref "U$6") (pin "P$17") (pinfunction "8-PWM_P$17") (pintype "bidirectional"))
    )
    (net (code "86") (name "Net-(U$6-9-PWM)") (class "Default")
      (node (ref "JP5") (pin "5") (pinfunction "5_5") (pintype "passive"))
      (node (ref "U$6") (pin "P$18") (pinfunction "9-PWM_P$18") (pintype "bidirectional"))
    )
    (net (code "87") (name "Net-(U$6-11-PWM)") (class "Default")
      (node (ref "JP5") (pin "4") (pinfunction "4_4") (pintype "passive"))
      (node (ref "U$6") (pin "P$20") (pinfunction "11-PWM_P$20") (pintype "bidirectional"))
    )
    (net (code "88") (name "Net-(U$6-12-PWM)") (class "Default")
      (node (ref "JP5") (pin "3") (pinfunction "3_3") (pintype "passive"))
      (node (ref "U$6") (pin "P$21") (pinfunction "12-PWM_P$21") (pintype "bidirectional"))
    )
    (net (code "89") (name "Net-(U$6-14-TX3)") (class "Default")
      (node (ref "JP8") (pin "2") (pinfunction "2_2") (pintype "passive"))
      (node (ref "U$6") (pin "P$23") (pinfunction "14-TX3_P$23") (pintype "bidirectional"))
    )
    (net (code "90") (name "Net-(U$6-16-TX2)") (class "Default")
      (node (ref "JP8") (pin "3") (pinfunction "3_3") (pintype "passive"))
      (node (ref "U$6") (pin "P$25") (pinfunction "16-TX2_P$25") (pintype "bidirectional"))
    )
    (net (code "91") (name "Net-(U$6-18-TX1)") (class "Default")
      (node (ref "JP8") (pin "4") (pinfunction "4_4") (pintype "passive"))
      (node (ref "U$6") (pin "P$27") (pinfunction "18-TX1_P$27") (pintype "bidirectional"))
    )
    (net (code "92") (name "Net-(U$6-D-22)") (class "Default")
      (node (ref "JP6") (pin "10") (pinfunction "10_10") (pintype "passive"))
      (node (ref "U$6") (pin "P$48") (pinfunction "D-22_P$48") (pintype "bidirectional"))
    )
    (net (code "93") (name "Net-(U$6-D-23)") (class "Default")
      (node (ref "JP6") (pin "9") (pinfunction "9_9") (pintype "passive"))
      (node (ref "U$6") (pin "P$49") (pinfunction "D-23_P$49") (pintype "bidirectional"))
    )
    (net (code "94") (name "Net-(U$6-D-24)") (class "Default")
      (node (ref "JP6") (pin "8") (pinfunction "8_8") (pintype "passive"))
      (node (ref "U$6") (pin "P$50") (pinfunction "D-24_P$50") (pintype "bidirectional"))
    )
    (net (code "95") (name "Net-(U$6-D-25)") (class "Default")
      (node (ref "JP6") (pin "7") (pinfunction "7_7") (pintype "passive"))
      (node (ref "U$6") (pin "P$51") (pinfunction "D-25_P$51") (pintype "bidirectional"))
    )
    (net (code "96") (name "Net-(U$6-D-26)") (class "Default")
      (node (ref "JP6") (pin "6") (pinfunction "6_6") (pintype "passive"))
      (node (ref "U$6") (pin "P$52") (pinfunction "D-26_P$52") (pintype "bidirectional"))
    )
    (net (code "97") (name "Net-(U$6-D-27)") (class "Default")
      (node (ref "JP6") (pin "5") (pinfunction "5_5") (pintype "passive"))
      (node (ref "U$6") (pin "P$53") (pinfunction "D-27_P$53") (pintype "bidirectional"))
    )
    (net (code "98") (name "Net-(U$6-D-28)") (class "Default")
      (node (ref "JP6") (pin "4") (pinfunction "4_4") (pintype "passive"))
      (node (ref "U$6") (pin "P$54") (pinfunction "D-28_P$54") (pintype "bidirectional"))
    )
    (net (code "99") (name "Net-(U$6-D-29)") (class "Default")
      (node (ref "JP6") (pin "3") (pinfunction "3_3") (pintype "passive"))
      (node (ref "U$6") (pin "P$55") (pinfunction "D-29_P$55") (pintype "bidirectional"))
    )
    (net (code "100") (name "Net-(U$6-D-32)") (class "Default")
      (node (ref "JP10") (pin "15") (pinfunction "15_15") (pintype "passive"))
      (node (ref "U$6") (pin "P$58") (pinfunction "D-32_P$58") (pintype "bidirectional"))
    )
    (net (code "101") (name "Net-(U$6-D-33)") (class "Default")
      (node (ref "JP10") (pin "14") (pinfunction "14_14") (pintype "passive"))
      (node (ref "U$6") (pin "P$59") (pinfunction "D-33_P$59") (pintype "bidirectional"))
    )
    (net (code "102") (name "Net-(U$6-D-34)") (class "Default")
      (node (ref "JP10") (pin "13") (pinfunction "13_13") (pintype "passive"))
      (node (ref "U$6") (pin "P$60") (pinfunction "D-34_P$60") (pintype "bidirectional"))
    )
    (net (code "103") (name "Net-(U$6-D-35)") (class "Default")
      (node (ref "JP10") (pin "12") (pinfunction "12_12") (pintype "passive"))
      (node (ref "U$6") (pin "P$61") (pinfunction "D-35_P$61") (pintype "bidirectional"))
    )
    (net (code "104") (name "Net-(U$6-D-36)") (class "Default")
      (node (ref "JP10") (pin "11") (pinfunction "11_11") (pintype "passive"))
      (node (ref "U$6") (pin "P$62") (pinfunction "D-36_P$62") (pintype "bidirectional"))
    )
    (net (code "105") (name "Net-(U$6-D-37)") (class "Default")
      (node (ref "JP10") (pin "10") (pinfunction "10_10") (pintype "passive"))
      (node (ref "U$6") (pin "P$63") (pinfunction "D-37_P$63") (pintype "bidirectional"))
    )
    (net (code "106") (name "Net-(U$6-D-38)") (class "Default")
      (node (ref "JP10") (pin "9") (pinfunction "9_9") (pintype "passive"))
      (node (ref "U$6") (pin "P$64") (pinfunction "D-38_P$64") (pintype "bidirectional"))
    )
    (net (code "107") (name "Net-(U$6-D-39)") (class "Default")
      (node (ref "JP10") (pin "8") (pinfunction "8_8") (pintype "passive"))
      (node (ref "U$6") (pin "P$65") (pinfunction "D-39_P$65") (pintype "bidirectional"))
    )
    (net (code "108") (name "Net-(U$6-D-40)") (class "Default")
      (node (ref "JP10") (pin "7") (pinfunction "7_7") (pintype "passive"))
      (node (ref "U$6") (pin "P$66") (pinfunction "D-40_P$66") (pintype "bidirectional"))
    )
    (net (code "109") (name "Net-(U$6-D-41)") (class "Default")
      (node (ref "JP10") (pin "6") (pinfunction "6_6") (pintype "passive"))
      (node (ref "U$6") (pin "P$67") (pinfunction "D-41_P$67") (pintype "bidirectional"))
    )
    (net (code "110") (name "Net-(U$6-D-42)") (class "Default")
      (node (ref "JP10") (pin "5") (pinfunction "5_5") (pintype "passive"))
      (node (ref "U$6") (pin "P$68") (pinfunction "D-42_P$68") (pintype "bidirectional"))
    )
    (net (code "111") (name "Net-(U$6-D-43)") (class "Default")
      (node (ref "JP10") (pin "4") (pinfunction "4_4") (pintype "passive"))
      (node (ref "U$6") (pin "P$69") (pinfunction "D-43_P$69") (pintype "bidirectional"))
    )
    (net (code "112") (name "Net-(U$6-D-44)") (class "Default")
      (node (ref "JP10") (pin "3") (pinfunction "3_3") (pintype "passive"))
      (node (ref "U$6") (pin "P$70") (pinfunction "D-44_P$70") (pintype "bidirectional"))
    )
    (net (code "113") (name "Net-(U$6-D-45)") (class "Default")
      (node (ref "JP10") (pin "2") (pinfunction "2_2") (pintype "passive"))
      (node (ref "U$6") (pin "P$71") (pinfunction "D-45_P$71") (pintype "bidirectional"))
    )
    (net (code "114") (name "Net-(U$6-D-46)") (class "Default")
      (node (ref "JP7") (pin "4") (pinfunction "4_4") (pintype "passive"))
      (node (ref "U$6") (pin "P$72") (pinfunction "D-46_P$72") (pintype "bidirectional"))
    )
    (net (code "115") (name "Net-(U$6-D-47)") (class "Default")
      (node (ref "JP7") (pin "3") (pinfunction "3_3") (pintype "passive"))
      (node (ref "U$6") (pin "P$73") (pinfunction "D-47_P$73") (pintype "bidirectional"))
    )
    (net (code "116") (name "Net-(U$6-D-48)") (class "Default")
      (node (ref "JP7") (pin "2") (pinfunction "2_2") (pintype "passive"))
      (node (ref "U$6") (pin "P$74") (pinfunction "D-48_P$74") (pintype "bidirectional"))
    )
    (net (code "117") (name "Net-(U$6-D-51)") (class "Default")
      (node (ref "JP5") (pin "2") (pinfunction "2_2") (pintype "passive"))
      (node (ref "U$6") (pin "P$77") (pinfunction "D-51_P$77") (pintype "bidirectional"))
    )
    (net (code "118") (name "Net-(U$6-D-52)") (class "Default")
      (node (ref "JP5") (pin "6") (pinfunction "6_6") (pintype "passive"))
      (node (ref "U$6") (pin "P$78") (pinfunction "D-52_P$78") (pintype "bidirectional"))
    )
    (net (code "119") (name "Net-(U1-BLANK)") (class "Default")
      (node (ref "JP9") (pin "5") (pinfunction "5_5") (pintype "passive"))
      (node (ref "R2") (pin "1") (pinfunction "1_1") (pintype "passive"))
      (node (ref "U1") (pin "23") (pinfunction "BLANK_23") (pintype "bidirectional"))
      (node (ref "U2") (pin "23") (pinfunction "BLANK_23") (pintype "bidirectional"))
    )
    (net (code "120") (name "Net-(U1-GND)") (class "Default")
      (node (ref "C2") (pin "2") (pinfunction "2_2") (pintype "passive"))
      (node (ref "C3") (pin "2") (pinfunction "2_2") (pintype "passive"))
      (node (ref "JP9") (pin "7") (pinfunction "7_7") (pintype "passive"))
      (node (ref "R1") (pin "2") (pinfunction "2_2") (pintype "passive"))
      (node (ref "R3") (pin "1") (pinfunction "1_1") (pintype "passive"))
      (node (ref "U1") (pin "22") (pinfunction "GND_22") (pintype "bidirectional"))
      (node (ref "U1") (pin "27") (pinfunction "VPRG_27") (pintype "bidirectional"))
      (node (ref "U2") (pin "22") (pinfunction "GND_22") (pintype "bidirectional"))
      (node (ref "U2") (pin "27") (pinfunction "VPRG_27") (pintype "bidirectional"))
    )
    (net (code "121") (name "Net-(U1-GSCLK)") (class "Default")
      (node (ref "JP9") (pin "3") (pinfunction "3_3") (pintype "passive"))
      (node (ref "U1") (pin "18") (pinfunction "GSCLK_18") (pintype "bidirectional"))
      (node (ref "U2") (pin "18") (pinfunction "GSCLK_18") (pintype "bidirectional"))
    )
    (net (code "122") (name "Net-(U1-IREF)") (class "Default")
      (node (ref "R1") (pin "1") (pinfunction "1_1") (pintype "passive"))
      (node (ref "U1") (pin "20") (pinfunction "IREF_20") (pintype "bidirectional"))
    )
    (net (code "123") (name "Net-(U1-SCLK)") (class "Default")
      (node (ref "JP9") (pin "2") (pinfunction "2_2") (pintype "passive"))
      (node (ref "U1") (pin "25") (pinfunction "SCLK_25") (pintype "bidirectional"))
      (node (ref "U2") (pin "25") (pinfunction "SCLK_25") (pintype "bidirectional"))
    )
    (net (code "124") (name "Net-(U1-SIN)") (class "Default")
      (node (ref "JP9") (pin "6") (pinfunction "6_6") (pintype "passive"))
      (node (ref "U1") (pin "26") (pinfunction "SIN_26") (pintype "bidirectional"))
    )
    (net (code "125") (name "Net-(U1-SOUT)") (class "Default")
      (node (ref "U1") (pin "17") (pinfunction "SOUT_17") (pintype "bidirectional"))
      (node (ref "U2") (pin "26") (pinfunction "SIN_26") (pintype "bidirectional"))
    )
    (net (code "126") (name "Net-(U1-XLAT)") (class "Default")
      (node (ref "JP9") (pin "4") (pinfunction "4_4") (pintype "passive"))
      (node (ref "U1") (pin "24") (pinfunction "XLAT_24") (pintype "bidirectional"))
      (node (ref "U2") (pin "24") (pinfunction "XLAT_24") (pintype "bidirectional"))
    )
    (net (code "127") (name "Net-(U2-IREF)") (class "Default")
      (node (ref "R3") (pin "2") (pinfunction "2_2") (pintype "passive"))
      (node (ref "U2") (pin "20") (pinfunction "IREF_20") (pintype "bidirectional"))
    )
    (net (code "128") (name "Net-(U2-OUT8)") (class "Default")
      (node (ref "R28") (pin "2") (pinfunction "2_2") (pintype "passive"))
      (node (ref "U2") (pin "8") (pinfunction "OUT8_8") (pintype "bidirectional"))
    )
    (net (code "129") (name "Net-(U2-OUT9)") (class "Default")
      (node (ref "R27") (pin "2") (pinfunction "2_2") (pintype "passive"))
      (node (ref "U2") (pin "9") (pinfunction "OUT9_9") (pintype "bidirectional"))
    )
    (net (code "130") (name "Net-(U2-OUT10)") (class "Default")
      (node (ref "R22") (pin "2") (pinfunction "2_2") (pintype "passive"))
      (node (ref "U2") (pin "10") (pinfunction "OUT10_10") (pintype "bidirectional"))
    )
    (net (code "131") (name "Net-(U2-OUT11)") (class "Default")
      (node (ref "R21") (pin "2") (pinfunction "2_2") (pintype "passive"))
      (node (ref "U2") (pin "11") (pinfunction "OUT11_11") (pintype "bidirectional"))
    )
    (net (code "132") (name "Net-(U2-OUT12)") (class "Default")
      (node (ref "R16") (pin "2") (pinfunction "2_2") (pintype "passive"))
      (node (ref "U2") (pin "12") (pinfunction "OUT12_12") (pintype "bidirectional"))
    )
    (net (code "133") (name "Net-(U2-OUT13)") (class "Default")
      (node (ref "R15") (pin "2") (pinfunction "2_2") (pintype "passive"))
      (node (ref "U2") (pin "13") (pinfunction "OUT13_13") (pintype "bidirectional"))
    )
    (net (code "134") (name "Net-(U2-OUT14)") (class "Default")
      (node (ref "R4") (pin "2") (pinfunction "2_2") (pintype "passive"))
      (node (ref "U2") (pin "14") (pinfunction "OUT14_14") (pintype "bidirectional"))
    )
    (net (code "135") (name "Net-(U2-OUT15)") (class "Default")
      (node (ref "R17") (pin "2") (pinfunction "2_2") (pintype "passive"))
      (node (ref "U2") (pin "15") (pinfunction "OUT15_15") (pintype "bidirectional"))
    )
    (net (code "136") (name "Net-(X2-A)") (class "Default")
      (node (ref "JP4") (pin "15") (pinfunction "15_15") (pintype "passive"))
      (node (ref "X2") (pin "15") (pinfunction "A_15") (pintype "input"))
    )
    (net (code "137") (name "Net-(X2-DB0)") (class "Default")
      (node (ref "JP4") (pin "7") (pinfunction "7_7") (pintype "passive"))
      (node (ref "X2") (pin "7") (pinfunction "DB0_7") (pintype "bidirectional"))
    )
    (net (code "138") (name "Net-(X2-DB1)") (class "Default")
      (node (ref "JP4") (pin "8") (pinfunction "8_8") (pintype "passive"))
      (node (ref "X2") (pin "8") (pinfunction "DB1_8") (pintype "bidirectional"))
    )
    (net (code "139") (name "Net-(X2-DB2)") (class "Default")
      (node (ref "JP4") (pin "9") (pinfunction "9_9") (pintype "passive"))
      (node (ref "X2") (pin "9") (pinfunction "DB2_9") (pintype "bidirectional"))
    )
    (net (code "140") (name "Net-(X2-DB3)") (class "Default")
      (node (ref "JP4") (pin "10") (pinfunction "10_10") (pintype "passive"))
      (node (ref "X2") (pin "10") (pinfunction "DB3_10") (pintype "bidirectional"))
    )
    (net (code "141") (name "Net-(X2-DB4)") (class "Default")
      (node (ref "JP4") (pin "11") (pinfunction "11_11") (pintype "passive"))
      (node (ref "X2") (pin "11") (pinfunction "DB4_11") (pintype "bidirectional"))
    )
    (net (code "142") (name "Net-(X2-DB5)") (class "Default")
      (node (ref "JP4") (pin "12") (pinfunction "12_12") (pintype "passive"))
      (node (ref "X2") (pin "12") (pinfunction "DB5_12") (pintype "bidirectional"))
    )
    (net (code "143") (name "Net-(X2-DB6)") (class "Default")
      (node (ref "JP4") (pin "13") (pinfunction "13_13") (pintype "passive"))
      (node (ref "X2") (pin "13") (pinfunction "DB6_13") (pintype "bidirectional"))
    )
    (net (code "144") (name "Net-(X2-DB7)") (class "Default")
      (node (ref "JP4") (pin "14") (pinfunction "14_14") (pintype "passive"))
      (node (ref "X2") (pin "14") (pinfunction "DB7_14") (pintype "bidirectional"))
    )
    (net (code "145") (name "Net-(X2-E)") (class "Default")
      (node (ref "JP4") (pin "6") (pinfunction "6_6") (pintype "passive"))
      (node (ref "X2") (pin "6") (pinfunction "E_6") (pintype "input"))
    )
    (net (code "146") (name "Net-(X2-K)") (class "Default")
      (node (ref "JP4") (pin "16") (pinfunction "16_16") (pintype "passive"))
      (node (ref "X2") (pin "16") (pinfunction "K_16") (pintype "input"))
    )
    (net (code "147") (name "Net-(X2-RS)") (class "Default")
      (node (ref "JP4") (pin "4") (pinfunction "4_4") (pintype "passive"))
      (node (ref "X2") (pin "4") (pinfunction "RS_4") (pintype "input"))
    )
    (net (code "148") (name "Net-(X2-RW)") (class "Default")
      (node (ref "JP4") (pin "5") (pinfunction "5_5") (pintype "passive"))
      (node (ref "X2") (pin "5") (pinfunction "RW_5") (pintype "input"))
    )
    (net (code "149") (name "Net-(X2-VDD)") (class "Default")
      (node (ref "JP4") (pin "2") (pinfunction "2_2") (pintype "passive"))
      (node (ref "X2") (pin "2") (pinfunction "VDD_2") (pintype "power_in"))
    )
    (net (code "150") (name "Net-(X2-VO)") (class "Default")
      (node (ref "JP4") (pin "3") (pinfunction "3_3") (pintype "passive"))
      (node (ref "X2") (pin "3") (pinfunction "VO_3") (pintype "input"))
    )
    (net (code "151") (name "Net-(X2-VSS)") (class "Default")
      (node (ref "JP4") (pin "1") (pinfunction "1_1") (pintype "passive"))
      (node (ref "X2") (pin "1") (pinfunction "VSS_1") (pintype "power_in"))
    )
    (net (code "152") (name "VCC") (class "Default")
      (node (ref "C1") (pin "2") (pinfunction "2_2") (pintype "passive"))
      (node (ref "C4") (pin "2") (pinfunction "2_2") (pintype "passive"))
      (node (ref "C5") (pin "1") (pinfunction "+_1") (pintype "passive"))
      (node (ref "JP5") (pin "7") (pinfunction "7_7") (pintype "passive"))
      (node (ref "JP6") (pin "15") (pinfunction "15_15") (pintype "passive"))
      (node (ref "JP8") (pin "6") (pinfunction "6_6") (pintype "passive"))
      (node (ref "R14") (pin "1") (pinfunction "1_1") (pintype "passive"))
      (node (ref "R31") (pin "1") (pinfunction "A_1") (pintype "passive"))
      (node (ref "U$6") (pin "P$13") (pinfunction "5V_P$13") (pintype "bidirectional"))
    )
    (net (code "153") (name "unconnected-(CHANNEL_1-P-Pad3)") (class "Default")
      (node (ref "CHANNEL_1") (pin "3") (pinfunction "P_3") (pintype "passive"))
    )
    (net (code "154") (name "unconnected-(CHANNEL_1-S-Pad1)") (class "Default")
      (node (ref "CHANNEL_1") (pin "1") (pinfunction "S_1") (pintype "passive"))
    )
    (net (code "155") (name "unconnected-(CHANNEL_2-P-Pad3)") (class "Default")
      (node (ref "CHANNEL_2") (pin "3") (pinfunction "P_3") (pintype "passive"))
    )
    (net (code "156") (name "unconnected-(CHANNEL_2-S-Pad1)") (class "Default")
      (node (ref "CHANNEL_2") (pin "1") (pinfunction "S_1") (pintype "passive"))
    )
    (net (code "157") (name "unconnected-(CHANNEL_3-P-Pad3)") (class "Default")
      (node (ref "CHANNEL_3") (pin "3") (pinfunction "P_3") (pintype "passive"))
    )
    (net (code "158") (name "unconnected-(CHANNEL_3-S-Pad1)") (class "Default")
      (node (ref "CHANNEL_3") (pin "1") (pinfunction "S_1") (pintype "passive"))
    )
    (net (code "159") (name "unconnected-(CHANNEL_4-P-Pad3)") (class "Default")
      (node (ref "CHANNEL_4") (pin "3") (pinfunction "P_3") (pintype "passive"))
    )
    (net (code "160") (name "unconnected-(CHANNEL_4-S-Pad1)") (class "Default")
      (node (ref "CHANNEL_4") (pin "1") (pinfunction "S_1") (pintype "passive"))
    )
    (net (code "161") (name "unconnected-(COUNT_DOWN-P-Pad3)") (class "Default")
      (node (ref "COUNT_DOWN") (pin "3") (pinfunction "P_3") (pintype "passive"))
    )
    (net (code "162") (name "unconnected-(COUNT_DOWN-S-Pad1)") (class "Default")
      (node (ref "COUNT_DOWN") (pin "1") (pinfunction "S_1") (pintype "passive"))
    )
    (net (code "163") (name "unconnected-(COUNT_UP-P-Pad3)") (class "Default")
      (node (ref "COUNT_UP") (pin "3") (pinfunction "P_3") (pintype "passive"))
    )
    (net (code "164") (name "unconnected-(COUNT_UP-S-Pad1)") (class "Default")
      (node (ref "COUNT_UP") (pin "1") (pinfunction "S_1") (pintype "passive"))
    )
    (net (code "165") (name "unconnected-(PLAY-P-Pad3)") (class "Default")
      (node (ref "PLAY") (pin "3") (pinfunction "P_3") (pintype "passive"))
    )
    (net (code "166") (name "unconnected-(PLAY-S-Pad1)") (class "Default")
      (node (ref "PLAY") (pin "1") (pinfunction "S_1") (pintype "passive"))
    )
    (net (code "167") (name "unconnected-(STOP-P-Pad3)") (class "Default")
      (node (ref "STOP") (pin "3") (pinfunction "P_3") (pintype "passive"))
    )
    (net (code "168") (name "unconnected-(STOP-S-Pad1)") (class "Default")
      (node (ref "STOP") (pin "1") (pinfunction "S_1") (pintype "passive"))
    )
    (net (code "169") (name "unconnected-(TEMPO_DOWN-P-Pad3)") (class "Default")
      (node (ref "TEMPO_DOWN") (pin "3") (pinfunction "P_3") (pintype "passive"))
    )
    (net (code "170") (name "unconnected-(TEMPO_DOWN-S-Pad1)") (class "Default")
      (node (ref "TEMPO_DOWN") (pin "1") (pinfunction "S_1") (pintype "passive"))
    )
    (net (code "171") (name "unconnected-(TEMPO_UP-P-Pad3)") (class "Default")
      (node (ref "TEMPO_UP") (pin "3") (pinfunction "P_3") (pintype "passive"))
    )
    (net (code "172") (name "unconnected-(TEMPO_UP-S-Pad1)") (class "Default")
      (node (ref "TEMPO_UP") (pin "1") (pinfunction "S_1") (pintype "passive"))
    )
    (net (code "173") (name "unconnected-(U$1-NC1-Pad3)") (class "Default")
      (node (ref "U$1") (pin "3") (pinfunction "NC1_3") (pintype "bidirectional"))
    )
    (net (code "174") (name "unconnected-(U$1-NC3-Pad1)") (class "Default")
      (node (ref "U$1") (pin "1") (pinfunction "NC3_1") (pintype "bidirectional"))
    )
    (net (code "175") (name "unconnected-(U$2-NC1-Pad3)") (class "Default")
      (node (ref "U$2") (pin "3") (pinfunction "NC1_3") (pintype "bidirectional"))
    )
    (net (code "176") (name "unconnected-(U$2-NC3-Pad1)") (class "Default")
      (node (ref "U$2") (pin "1") (pinfunction "NC3_1") (pintype "bidirectional"))
    )
    (net (code "177") (name "unconnected-(U$3-NC1-Pad3)") (class "Default")
      (node (ref "U$3") (pin "3") (pinfunction "NC1_3") (pintype "bidirectional"))
    )
    (net (code "178") (name "unconnected-(U$3-NC3-Pad1)") (class "Default")
      (node (ref "U$3") (pin "1") (pinfunction "NC3_1") (pintype "bidirectional"))
    )
    (net (code "179") (name "unconnected-(U$4-NC1-Pad3)") (class "Default")
      (node (ref "U$4") (pin "3") (pinfunction "NC1_3") (pintype "bidirectional"))
    )
    (net (code "180") (name "unconnected-(U$4-NC3-Pad1)") (class "Default")
      (node (ref "U$4") (pin "1") (pinfunction "NC3_1") (pintype "bidirectional"))
    )
    (net (code "181") (name "unconnected-(U$6-0-RX0-PadP$1)") (class "Default")
      (node (ref "U$6") (pin "P$1") (pinfunction "0-RX0_P$1") (pintype "bidirectional"))
    )
    (net (code "182") (name "unconnected-(U$6-1-ICSP(MISO)-PadP$2)") (class "Default")
      (node (ref "U$6") (pin "P$2") (pinfunction "1-ICSP(MISO)_P$2") (pintype "bidirectional"))
    )
    (net (code "183") (name "unconnected-(U$6-2-ICSP(5V)-PadP$4)") (class "Default")
      (node (ref "U$6") (pin "P$4") (pinfunction "2-ICSP(5V)_P$4") (pintype "bidirectional"))
    )
    (net (code "184") (name "unconnected-(U$6-2-PWM-PadP$5)") (class "Default")
      (node (ref "U$6") (pin "P$5") (pinfunction "2-PWM_P$5") (pintype "bidirectional"))
    )
    (net (code "185") (name "unconnected-(U$6-3-ICSP(SCK)-PadP$6)") (class "Default")
      (node (ref "U$6") (pin "P$6") (pinfunction "3-ICSP(SCK)_P$6") (pintype "bidirectional"))
    )
    (net (code "186") (name "unconnected-(U$6-3-PWM-PadP$7)") (class "Default")
      (node (ref "U$6") (pin "P$7") (pinfunction "3-PWM_P$7") (pintype "bidirectional"))
    )
    (net (code "187") (name "unconnected-(U$6-3.3V-PadP$8)") (class "Default")
      (node (ref "U$6") (pin "P$8") (pinfunction "3.3V_P$8") (pintype "bidirectional"))
    )
    (net (code "188") (name "unconnected-(U$6-4-ICSP(MOSI)-PadP$9)") (class "Default")
      (node (ref "U$6") (pin "P$9") (pinfunction "4-ICSP(MOSI)_P$9") (pintype "bidirectional"))
    )
    (net (code "189") (name "unconnected-(U$6-4-PWM-PadP$10)") (class "Default")
      (node (ref "U$6") (pin "P$10") (pinfunction "4-PWM_P$10") (pintype "bidirectional"))
    )
    (net (code "190") (name "unconnected-(U$6-5-ICSP(RESET)-PadP$11)") (class "Default")
      (node (ref "U$6") (pin "P$11") (pinfunction "5-ICSP(RESET)_P$11") (pintype "bidirectional"))
    )
    (net (code "191") (name "unconnected-(U$6-5-PWM-PadP$12)") (class "Default")
      (node (ref "U$6") (pin "P$12") (pinfunction "5-PWM_P$12") (pintype "bidirectional"))
    )
    (net (code "192") (name "unconnected-(U$6-6-ICSP(GND)-PadP$14)") (class "Default")
      (node (ref "U$6") (pin "P$14") (pinfunction "6-ICSP(GND)_P$14") (pintype "bidirectional"))
    )
    (net (code "193") (name "unconnected-(U$6-10-PWM-PadP$19)") (class "Default")
      (node (ref "U$6") (pin "P$19") (pinfunction "10-PWM_P$19") (pintype "bidirectional"))
    )
    (net (code "194") (name "unconnected-(U$6-13-PWM-PadP$22)") (class "Default")
      (node (ref "U$6") (pin "P$22") (pinfunction "13-PWM_P$22") (pintype "bidirectional"))
    )
    (net (code "195") (name "unconnected-(U$6-15-RX3-PadP$24)") (class "Default")
      (node (ref "U$6") (pin "P$24") (pinfunction "15-RX3_P$24") (pintype "bidirectional"))
    )
    (net (code "196") (name "unconnected-(U$6-17-RX2-PadP$26)") (class "Default")
      (node (ref "U$6") (pin "P$26") (pinfunction "17-RX2_P$26") (pintype "bidirectional"))
    )
    (net (code "197") (name "unconnected-(U$6-19-RX1-PadP$28)") (class "Default")
      (node (ref "U$6") (pin "P$28") (pinfunction "19-RX1_P$28") (pintype "bidirectional"))
    )
    (net (code "198") (name "unconnected-(U$6-A-0-PadP$29)") (class "Default")
      (node (ref "U$6") (pin "P$29") (pinfunction "A-0_P$29") (pintype "bidirectional"))
    )
    (net (code "199") (name "unconnected-(U$6-A-1-PadP$30)") (class "Default")
      (node (ref "U$6") (pin "P$30") (pinfunction "A-1_P$30") (pintype "bidirectional"))
    )
    (net (code "200") (name "unconnected-(U$6-A-2-PadP$31)") (class "Default")
      (node (ref "U$6") (pin "P$31") (pinfunction "A-2_P$31") (pintype "bidirectional"))
    )
    (net (code "201") (name "unconnected-(U$6-A-3-PadP$32)") (class "Default")
      (node (ref "U$6") (pin "P$32") (pinfunction "A-3_P$32") (pintype "bidirectional"))
    )
    (net (code "202") (name "unconnected-(U$6-A-4-PadP$33)") (class "Default")
      (node (ref "U$6") (pin "P$33") (pinfunction "A-4_P$33") (pintype "bidirectional"))
    )
    (net (code "203") (name "unconnected-(U$6-A-5-PadP$34)") (class "Default")
      (node (ref "U$6") (pin "P$34") (pinfunction "A-5_P$34") (pintype "bidirectional"))
    )
    (net (code "204") (name "unconnected-(U$6-A-6-PadP$35)") (class "Default")
      (node (ref "U$6") (pin "P$35") (pinfunction "A-6_P$35") (pintype "bidirectional"))
    )
    (net (code "205") (name "unconnected-(U$6-A-7-PadP$36)") (class "Default")
      (node (ref "U$6") (pin "P$36") (pinfunction "A-7_P$36") (pintype "bidirectional"))
    )
    (net (code "206") (name "unconnected-(U$6-A-8-PadP$37)") (class "Default")
      (node (ref "U$6") (pin "P$37") (pinfunction "A-8_P$37") (pintype "bidirectional"))
    )
    (net (code "207") (name "unconnected-(U$6-A-9-PadP$38)") (class "Default")
      (node (ref "U$6") (pin "P$38") (pinfunction "A-9_P$38") (pintype "bidirectional"))
    )
    (net (code "208") (name "unconnected-(U$6-A-10-PadP$39)") (class "Default")
      (node (ref "U$6") (pin "P$39") (pinfunction "A-10_P$39") (pintype "bidirectional"))
    )
    (net (code "209") (name "unconnected-(U$6-A-11-PadP$40)") (class "Default")
      (node (ref "U$6") (pin "P$40") (pinfunction "A-11_P$40") (pintype "bidirectional"))
    )
    (net (code "210") (name "unconnected-(U$6-A-12-PadP$41)") (class "Default")
      (node (ref "U$6") (pin "P$41") (pinfunction "A-12_P$41") (pintype "bidirectional"))
    )
    (net (code "211") (name "unconnected-(U$6-A-13-PadP$42)") (class "Default")
      (node (ref "U$6") (pin "P$42") (pinfunction "A-13_P$42") (pintype "bidirectional"))
    )
    (net (code "212") (name "unconnected-(U$6-A-14-PadP$43)") (class "Default")
      (node (ref "U$6") (pin "P$43") (pinfunction "A-14_P$43") (pintype "bidirectional"))
    )
    (net (code "213") (name "unconnected-(U$6-A-15-PadP$44)") (class "Default")
      (node (ref "U$6") (pin "P$44") (pinfunction "A-15_P$44") (pintype "bidirectional"))
    )
    (net (code "214") (name "unconnected-(U$6-AREF-PadP$45)") (class "Default")
      (node (ref "U$6") (pin "P$45") (pinfunction "AREF_P$45") (pintype "bidirectional"))
    )
    (net (code "215") (name "unconnected-(U$6-D-30-PadP$56)") (class "Default")
      (node (ref "U$6") (pin "P$56") (pinfunction "D-30_P$56") (pintype "bidirectional"))
    )
    (net (code "216") (name "unconnected-(U$6-D-31-PadP$57)") (class "Default")
      (node (ref "U$6") (pin "P$57") (pinfunction "D-31_P$57") (pintype "bidirectional"))
    )
    (net (code "217") (name "unconnected-(U$6-D-49-PadP$75)") (class "Default")
      (node (ref "U$6") (pin "P$75") (pinfunction "D-49_P$75") (pintype "bidirectional"))
    )
    (net (code "218") (name "unconnected-(U$6-D-50-PadP$76)") (class "Default")
      (node (ref "U$6") (pin "P$76") (pinfunction "D-50_P$76") (pintype "bidirectional"))
    )
    (net (code "219") (name "unconnected-(U$6-D-53-PadP$79)") (class "Default")
      (node (ref "U$6") (pin "P$79") (pinfunction "D-53_P$79") (pintype "bidirectional"))
    )
    (net (code "220") (name "unconnected-(U$6-RESET-PadP$81)") (class "Default")
      (node (ref "U$6") (pin "P$81") (pinfunction "RESET_P$81") (pintype "bidirectional"))
    )
    (net (code "221") (name "unconnected-(U$6-SCL-21-PadP$47)") (class "Default")
      (node (ref "U$6") (pin "P$47") (pinfunction "SCL-21_P$47") (pintype "bidirectional"))
    )
    (net (code "222") (name "unconnected-(U$6-SDA-20-PadP$46)") (class "Default")
      (node (ref "U$6") (pin "P$46") (pinfunction "SDA-20_P$46") (pintype "bidirectional"))
    )
    (net (code "223") (name "unconnected-(U$6-VIN-PadP$82)") (class "Default")
      (node (ref "U$6") (pin "P$82") (pinfunction "VIN_P$82") (pintype "bidirectional"))
    )
    (net (code "224") (name "unconnected-(U1-XERR-Pad16)") (class "Default")
      (node (ref "U1") (pin "16") (pinfunction "XERR_16") (pintype "bidirectional"))
    )
    (net (code "225") (name "unconnected-(U2-SOUT-Pad17)") (class "Default")
      (node (ref "U2") (pin "17") (pinfunction "SOUT_17") (pintype "bidirectional"))
    )
    (net (code "226") (name "unconnected-(U2-XERR-Pad16)") (class "Default")
      (node (ref "U2") (pin "16") (pinfunction "XERR_16") (pintype "bidirectional"))
    )
  )
)
